# FPGA.net
KiCad netlist of a schematic drawn in Altium Designer
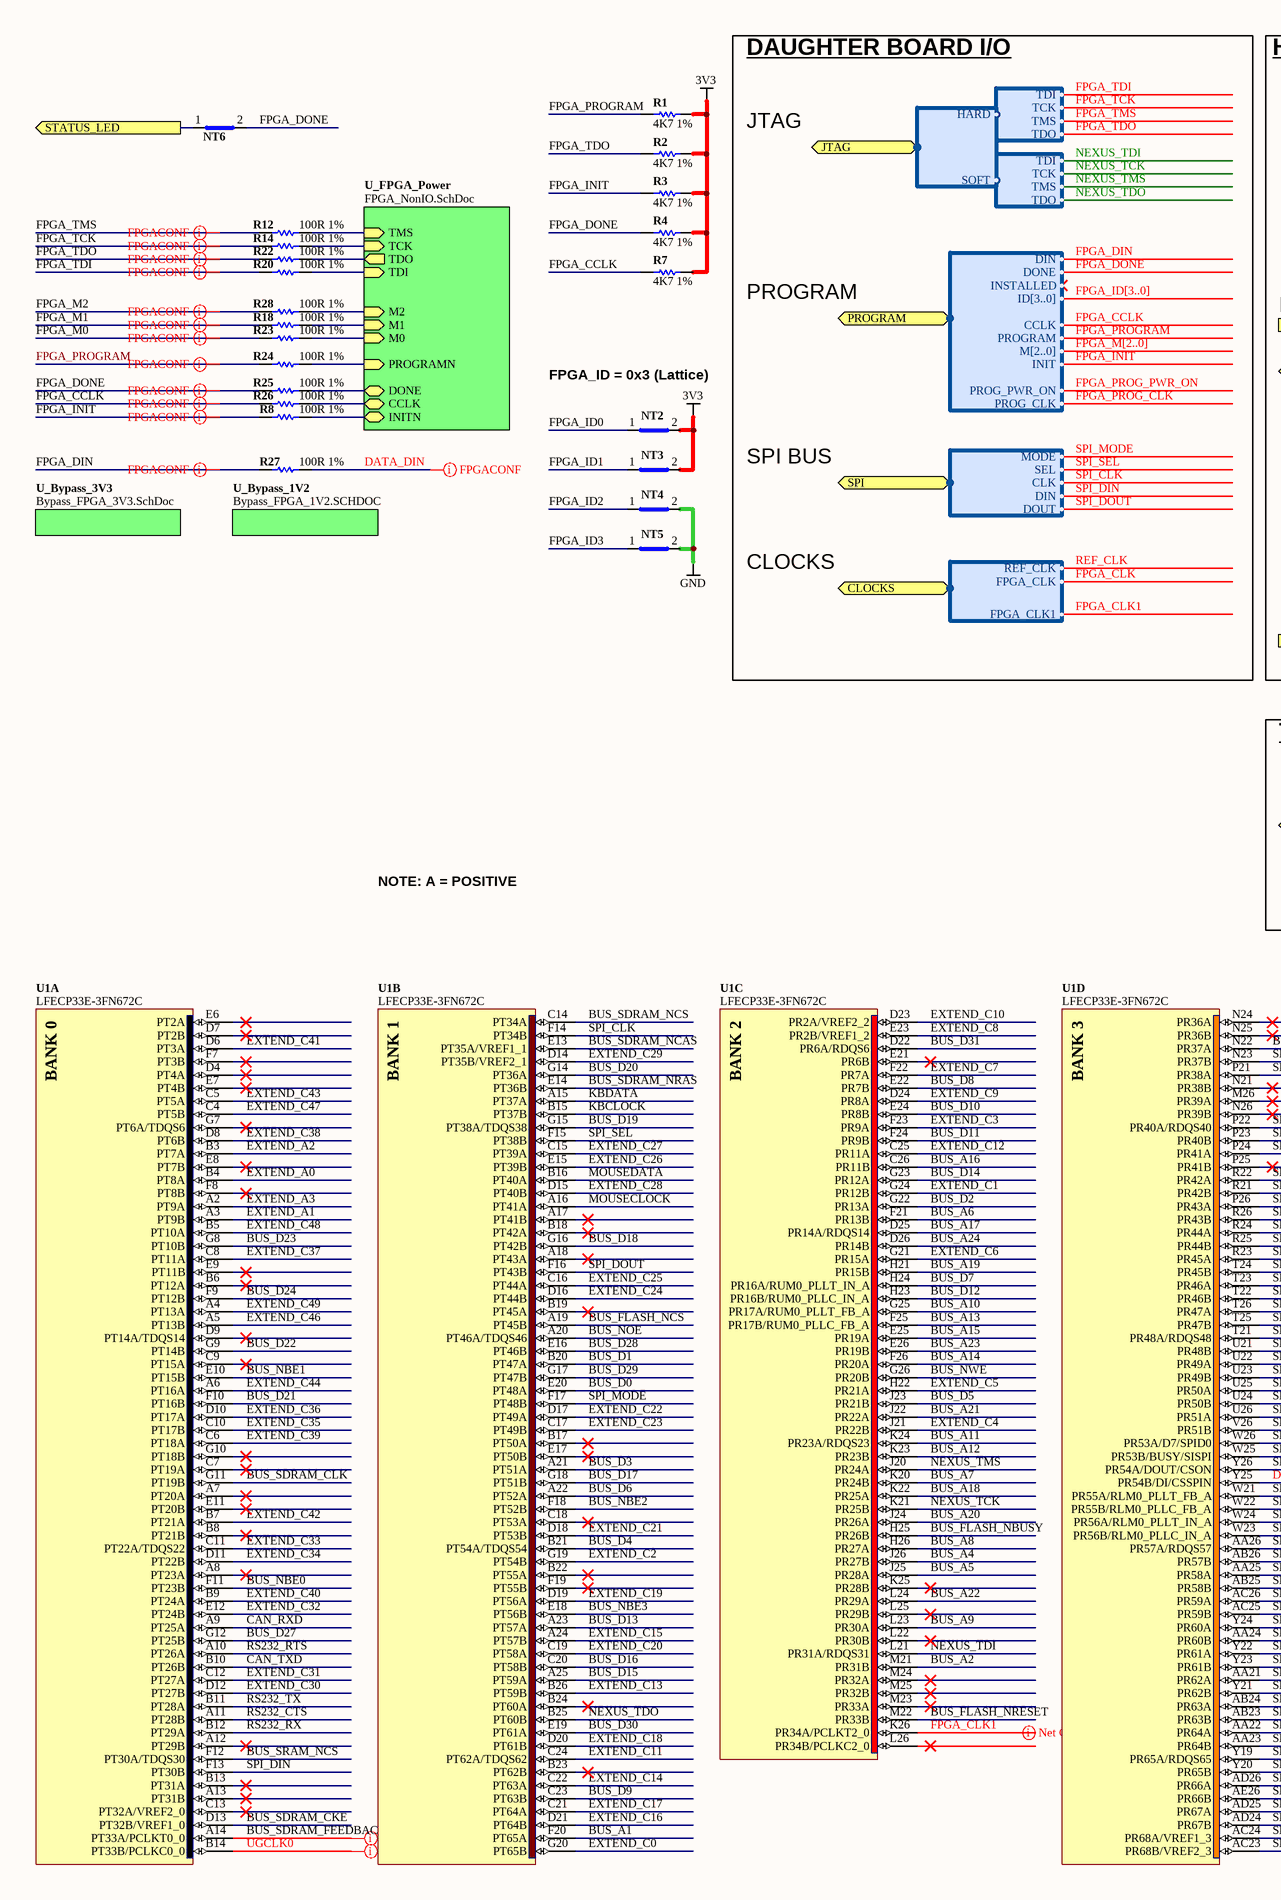
[diagram p0: FPGA.SCHDOC, left]
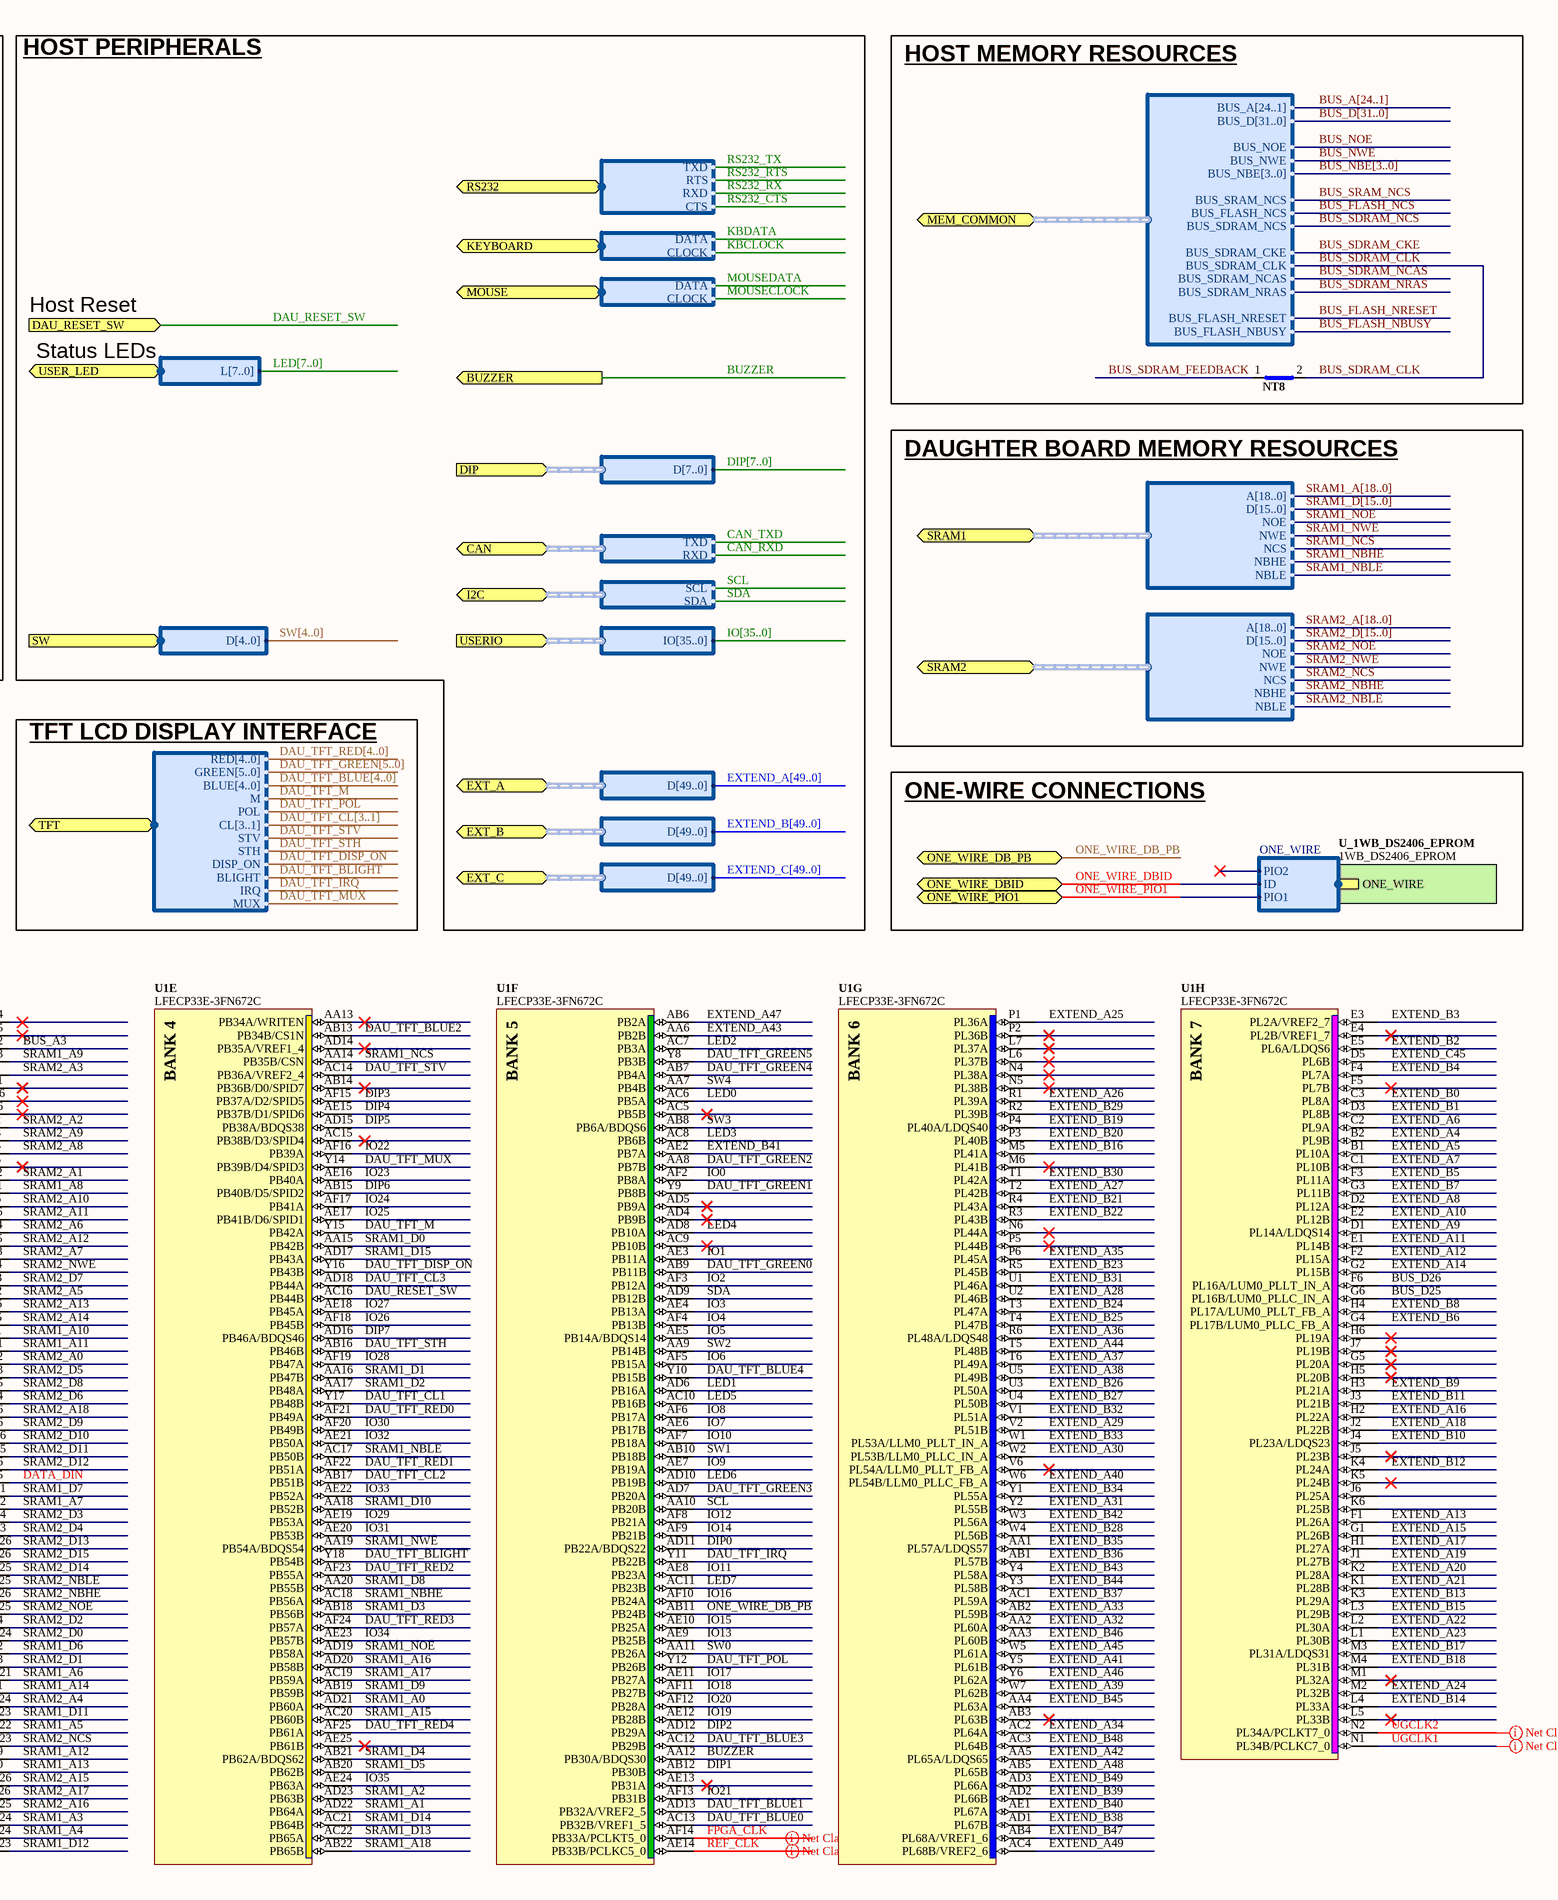
[diagram p1: FPGA.SCHDOC, right]

(export (version "E")
  (design (tool "Eeschema 10.0.6"))
  (components
    (comp (ref "NT2")
      (value "Net Tie SMT2")
      (footprint "NETTIE-SMT2-8X8")
      (description "Net-Tie, Surface Mount, 2 x 0.4mm x 0.2mm SMT Pads - For 0.2mm Track")
      (libsource (lib "AltiumDesignLibrary") (part "NETTIE-SMT2"))
    )
    (comp (ref "NT3")
      (value "Net Tie SMT2")
      (footprint "NETTIE-SMT2-8X8")
      (description "Net-Tie, Surface Mount, 2 x 0.4mm x 0.2mm SMT Pads - For 0.2mm Track")
      (libsource (lib "AltiumDesignLibrary") (part "NETTIE-SMT2"))
    )
    (comp (ref "NT4")
      (value "Net Tie SMT2")
      (footprint "NETTIE-SMT2-8X8")
      (description "Net-Tie, Surface Mount, 2 x 0.4mm x 0.2mm SMT Pads - For 0.2mm Track")
      (libsource (lib "AltiumDesignLibrary") (part "NETTIE-SMT2"))
    )
    (comp (ref "NT5")
      (value "Net Tie SMT2")
      (footprint "NETTIE-SMT2-8X8")
      (description "Net-Tie, Surface Mount, 2 x 0.4mm x 0.2mm SMT Pads - For 0.2mm Track")
      (libsource (lib "AltiumDesignLibrary") (part "NETTIE-SMT2"))
    )
    (comp (ref "NT6")
      (value "Net Tie SMT2")
      (footprint "NETTIE-SMT2-8X8")
      (description "Net-Tie, Surface Mount, 2 x 0.4mm x 0.2mm SMT Pads - For 0.2mm Track")
      (libsource (lib "AltiumDesignLibrary") (part "NETTIE-SMT2"))
    )
    (comp (ref "NT8")
      (value "Net Tie SMT2")
      (footprint "NETTIE-SMT2-8X8")
      (description "Net-Tie, Surface Mount, 2 x 0.4mm x 0.2mm SMT Pads - For 0.2mm Track")
      (libsource (lib "AltiumDesignLibrary") (part "NETTIE-SMT2"))
    )
    (comp (ref "R1")
      (value "4K7 1%")
      (footprint "RESC1005-STAR")
      (description "Resistor, 4K7 1% 0402 (1005)")
      (fields (field (name "TOLERANCE") "1 %"))
      (libsource (lib "AltiumDesignLibrary") (part "RES"))
    )
    (comp (ref "R2")
      (value "4K7 1%")
      (footprint "RESC1005-STAR")
      (description "Resistor, 4K7 1% 0402 (1005)")
      (fields (field (name "TOLERANCE") "1 %"))
      (libsource (lib "AltiumDesignLibrary") (part "RES"))
    )
    (comp (ref "R3")
      (value "4K7 1%")
      (footprint "RESC1005-STAR")
      (description "Resistor, 4K7 1% 0402 (1005)")
      (fields (field (name "TOLERANCE") "1 %"))
      (libsource (lib "AltiumDesignLibrary") (part "RES"))
    )
    (comp (ref "R4")
      (value "4K7 1%")
      (footprint "RESC1005-STAR")
      (description "Resistor, 4K7 1% 0402 (1005)")
      (fields (field (name "TOLERANCE") "1 %"))
      (libsource (lib "AltiumDesignLibrary") (part "RES"))
    )
    (comp (ref "R7")
      (value "4K7 1%")
      (footprint "RESC1005-STAR")
      (description "Resistor, 4K7 1% 0402 (1005)")
      (fields (field (name "TOLERANCE") "1 %"))
      (libsource (lib "AltiumDesignLibrary") (part "RES"))
    )
    (comp (ref "R8")
      (value "100R 1%")
      (footprint "RESC1005-STAR")
      (description "Resistor, 100R 1% 0402 (1005)")
      (fields (field (name "TOLERANCE") "1 %"))
      (libsource (lib "AltiumDesignLibrary") (part "RES"))
    )
    (comp (ref "R12")
      (value "100R 1%")
      (footprint "RESC1005-STAR")
      (description "Resistor, 100R 1% 0402 (1005)")
      (fields (field (name "TOLERANCE") "1 %"))
      (libsource (lib "AltiumDesignLibrary") (part "RES"))
    )
    (comp (ref "R14")
      (value "100R 1%")
      (footprint "RESC1005-STAR")
      (description "Resistor, 100R 1% 0402 (1005)")
      (fields (field (name "TOLERANCE") "1 %"))
      (libsource (lib "AltiumDesignLibrary") (part "RES"))
    )
    (comp (ref "R18")
      (value "100R 1%")
      (footprint "RESC1005-STAR")
      (description "Resistor, 100R 1% 0402 (1005)")
      (fields (field (name "TOLERANCE") "1 %"))
      (libsource (lib "AltiumDesignLibrary") (part "RES"))
    )
    (comp (ref "R20")
      (value "100R 1%")
      (footprint "RESC1005-STAR")
      (description "Resistor, 100R 1% 0402 (1005)")
      (fields (field (name "TOLERANCE") "1 %"))
      (libsource (lib "AltiumDesignLibrary") (part "RES"))
    )
    (comp (ref "R22")
      (value "100R 1%")
      (footprint "RESC1005-STAR")
      (description "Resistor, 100R 1% 0402 (1005)")
      (fields (field (name "TOLERANCE") "1 %"))
      (libsource (lib "AltiumDesignLibrary") (part "RES"))
    )
    (comp (ref "R23")
      (value "100R 1%")
      (footprint "RESC1005-STAR")
      (description "Resistor, 100R 1% 0402 (1005)")
      (fields (field (name "TOLERANCE") "1 %"))
      (libsource (lib "AltiumDesignLibrary") (part "RES"))
    )
    (comp (ref "R24")
      (value "100R 1%")
      (footprint "RESC1005-STAR")
      (description "Resistor, 100R 1% 0402 (1005)")
      (fields (field (name "TOLERANCE") "1 %"))
      (libsource (lib "AltiumDesignLibrary") (part "RES"))
    )
    (comp (ref "R25")
      (value "100R 1%")
      (footprint "RESC1005-STAR")
      (description "Resistor, 100R 1% 0402 (1005)")
      (fields (field (name "TOLERANCE") "1 %"))
      (libsource (lib "AltiumDesignLibrary") (part "RES"))
    )
    (comp (ref "R26")
      (value "100R 1%")
      (footprint "RESC1005-STAR")
      (description "Resistor, 100R 1% 0402 (1005)")
      (fields (field (name "TOLERANCE") "1 %"))
      (libsource (lib "AltiumDesignLibrary") (part "RES"))
    )
    (comp (ref "R27")
      (value "100R 1%")
      (footprint "RESC1005-STAR")
      (description "Resistor, 100R 1% 0402 (1005)")
      (fields (field (name "TOLERANCE") "1 %"))
      (libsource (lib "AltiumDesignLibrary") (part "RES"))
    )
    (comp (ref "R28")
      (value "100R 1%")
      (footprint "RESC1005-STAR")
      (description "Resistor, 100R 1% 0402 (1005)")
      (fields (field (name "TOLERANCE") "1 %"))
      (libsource (lib "AltiumDesignLibrary") (part "RES"))
    )
    (comp (ref "U1")
      (value "LFECP33E-3FN672C")
      (footprint "BGA100P26X26-672")
      (description "FPGA, Lattice ECP-35 FN672")
      (libsource (lib "AltiumDesignLibrary") (part "LFECP33E-3FN672C"))
    )
  )
  (nets
    (net (code "18") (name "/BUS_A1") (class "Default")
      (node (ref "U1") (pin "F20") (pinfunction "PT65A_F20") (pintype "bidirectional"))
    )
    (net (code "19") (name "/BUS_A2") (class "Default")
      (node (ref "U1") (pin "M21") (pinfunction "PR31B_M21") (pintype "bidirectional"))
    )
    (net (code "20") (name "/BUS_A3") (class "Default")
      (node (ref "U1") (pin "N22") (pinfunction "PR37A_N22") (pintype "bidirectional"))
    )
    (net (code "21") (name "/BUS_A4") (class "Default")
      (node (ref "U1") (pin "J26") (pinfunction "PR27B_J26") (pintype "bidirectional"))
    )
    (net (code "22") (name "/BUS_A5") (class "Default")
      (node (ref "U1") (pin "J25") (pinfunction "PR28A_J25") (pintype "bidirectional"))
    )
    (net (code "23") (name "/BUS_A6") (class "Default")
      (node (ref "U1") (pin "F21") (pinfunction "PR13B_F21") (pintype "bidirectional"))
    )
    (net (code "24") (name "/BUS_A7") (class "Default")
      (node (ref "U1") (pin "K20") (pinfunction "PR24B_K20") (pintype "bidirectional"))
    )
    (net (code "25") (name "/BUS_A8") (class "Default")
      (node (ref "U1") (pin "H26") (pinfunction "PR27A_H26") (pintype "bidirectional"))
    )
    (net (code "26") (name "/BUS_A9") (class "Default")
      (node (ref "U1") (pin "L23") (pinfunction "PR30A_L23") (pintype "bidirectional"))
    )
    (net (code "27") (name "/BUS_A10") (class "Default")
      (node (ref "U1") (pin "G25") (pinfunction "PR17A/RUM0_PLLT_FB_A_G25") (pintype "bidirectional"))
    )
    (net (code "28") (name "/BUS_A11") (class "Default")
      (node (ref "U1") (pin "K24") (pinfunction "PR23A/RDQS23_K24") (pintype "bidirectional"))
    )
    (net (code "29") (name "/BUS_A12") (class "Default")
      (node (ref "U1") (pin "K23") (pinfunction "PR23B_K23") (pintype "bidirectional"))
    )
    (net (code "30") (name "/BUS_A13") (class "Default")
      (node (ref "U1") (pin "F25") (pinfunction "PR17B/RUM0_PLLC_FB_A_F25") (pintype "bidirectional"))
    )
    (net (code "31") (name "/BUS_A14") (class "Default")
      (node (ref "U1") (pin "F26") (pinfunction "PR20A_F26") (pintype "bidirectional"))
    )
    (net (code "32") (name "/BUS_A15") (class "Default")
      (node (ref "U1") (pin "E25") (pinfunction "PR19A_E25") (pintype "bidirectional"))
    )
    (net (code "33") (name "/BUS_A16") (class "Default")
      (node (ref "U1") (pin "C26") (pinfunction "PR11B_C26") (pintype "bidirectional"))
    )
    (net (code "34") (name "/BUS_A17") (class "Default")
      (node (ref "U1") (pin "D25") (pinfunction "PR14A/RDQS14_D25") (pintype "bidirectional"))
    )
    (net (code "35") (name "/BUS_A18") (class "Default")
      (node (ref "U1") (pin "K22") (pinfunction "PR25A_K22") (pintype "bidirectional"))
    )
    (net (code "36") (name "/BUS_A19") (class "Default")
      (node (ref "U1") (pin "H21") (pinfunction "PR15B_H21") (pintype "bidirectional"))
    )
    (net (code "37") (name "/BUS_A20") (class "Default")
      (node (ref "U1") (pin "J24") (pinfunction "PR26A_J24") (pintype "bidirectional"))
    )
    (net (code "38") (name "/BUS_A21") (class "Default")
      (node (ref "U1") (pin "J22") (pinfunction "PR22A_J22") (pintype "bidirectional"))
    )
    (net (code "39") (name "/BUS_A22") (class "Default")
      (node (ref "U1") (pin "L24") (pinfunction "PR29A_L24") (pintype "bidirectional"))
    )
    (net (code "40") (name "/BUS_A23") (class "Default")
      (node (ref "U1") (pin "E26") (pinfunction "PR19B_E26") (pintype "bidirectional"))
    )
    (net (code "41") (name "/BUS_A24") (class "Default")
      (node (ref "U1") (pin "D26") (pinfunction "PR14B_D26") (pintype "bidirectional"))
    )
    (net (code "42") (name "/BUS_D0") (class "Default")
      (node (ref "U1") (pin "E20") (pinfunction "PT48A_E20") (pintype "bidirectional"))
    )
    (net (code "43") (name "/BUS_D1") (class "Default")
      (node (ref "U1") (pin "B20") (pinfunction "PT47A_B20") (pintype "bidirectional"))
    )
    (net (code "44") (name "/BUS_D2") (class "Default")
      (node (ref "U1") (pin "G22") (pinfunction "PR13A_G22") (pintype "bidirectional"))
    )
    (net (code "45") (name "/BUS_D3") (class "Default")
      (node (ref "U1") (pin "A21") (pinfunction "PT51A_A21") (pintype "bidirectional"))
    )
    (net (code "46") (name "/BUS_D4") (class "Default")
      (node (ref "U1") (pin "B21") (pinfunction "PT54A/TDQS54_B21") (pintype "bidirectional"))
    )
    (net (code "47") (name "/BUS_D5") (class "Default")
      (node (ref "U1") (pin "J23") (pinfunction "PR21B_J23") (pintype "bidirectional"))
    )
    (net (code "48") (name "/BUS_D6") (class "Default")
      (node (ref "U1") (pin "A22") (pinfunction "PT52A_A22") (pintype "bidirectional"))
    )
    (net (code "49") (name "/BUS_D7") (class "Default")
      (node (ref "U1") (pin "H24") (pinfunction "PR16A/RUM0_PLLT_IN_A_H24") (pintype "bidirectional"))
    )
    (net (code "50") (name "/BUS_D8") (class "Default")
      (node (ref "U1") (pin "E22") (pinfunction "PR7B_E22") (pintype "bidirectional"))
    )
    (net (code "51") (name "/BUS_D9") (class "Default")
      (node (ref "U1") (pin "C23") (pinfunction "PT63B_C23") (pintype "bidirectional"))
    )
    (net (code "52") (name "/BUS_D10") (class "Default")
      (node (ref "U1") (pin "E24") (pinfunction "PR8B_E24") (pintype "bidirectional"))
    )
    (net (code "53") (name "/BUS_D11") (class "Default")
      (node (ref "U1") (pin "F24") (pinfunction "PR9B_F24") (pintype "bidirectional"))
    )
    (net (code "54") (name "/BUS_D12") (class "Default")
      (node (ref "U1") (pin "H23") (pinfunction "PR16B/RUM0_PLLC_IN_A_H23") (pintype "bidirectional"))
    )
    (net (code "55") (name "/BUS_D13") (class "Default")
      (node (ref "U1") (pin "A23") (pinfunction "PT57A_A23") (pintype "bidirectional"))
    )
    (net (code "56") (name "/BUS_D14") (class "Default")
      (node (ref "U1") (pin "G23") (pinfunction "PR12A_G23") (pintype "bidirectional"))
    )
    (net (code "57") (name "/BUS_D15") (class "Default")
      (node (ref "U1") (pin "A25") (pinfunction "PT59A_A25") (pintype "bidirectional"))
    )
    (net (code "58") (name "/BUS_D16") (class "Default")
      (node (ref "U1") (pin "C20") (pinfunction "PT58B_C20") (pintype "bidirectional"))
    )
    (net (code "59") (name "/BUS_D17") (class "Default")
      (node (ref "U1") (pin "G18") (pinfunction "PT51B_G18") (pintype "bidirectional"))
    )
    (net (code "60") (name "/BUS_D18") (class "Default")
      (node (ref "U1") (pin "G16") (pinfunction "PT42B_G16") (pintype "bidirectional"))
    )
    (net (code "61") (name "/BUS_D19") (class "Default")
      (node (ref "U1") (pin "G15") (pinfunction "PT38A/TDQS38_G15") (pintype "bidirectional"))
    )
    (net (code "62") (name "/BUS_D20") (class "Default")
      (node (ref "U1") (pin "G14") (pinfunction "PT36A_G14") (pintype "bidirectional"))
    )
    (net (code "63") (name "/BUS_D21") (class "Default")
      (node (ref "U1") (pin "F10") (pinfunction "PT16B_F10") (pintype "bidirectional"))
    )
    (net (code "64") (name "/BUS_D22") (class "Default")
      (node (ref "U1") (pin "G9") (pinfunction "PT14B_G9") (pintype "bidirectional"))
    )
    (net (code "65") (name "/BUS_D23") (class "Default")
      (node (ref "U1") (pin "G8") (pinfunction "PT10B_G8") (pintype "bidirectional"))
    )
    (net (code "66") (name "/BUS_D24") (class "Default")
      (node (ref "U1") (pin "F9") (pinfunction "PT12B_F9") (pintype "bidirectional"))
    )
    (net (code "67") (name "/BUS_D25") (class "Default")
      (node (ref "U1") (pin "G6") (pinfunction "PL16B/LUM0_PLLC_IN_A_G6") (pintype "bidirectional"))
    )
    (net (code "68") (name "/BUS_D26") (class "Default")
      (node (ref "U1") (pin "F6") (pinfunction "PL16A/LUM0_PLLT_IN_A_F6") (pintype "bidirectional"))
    )
    (net (code "69") (name "/BUS_D27") (class "Default")
      (node (ref "U1") (pin "G12") (pinfunction "PT25B_G12") (pintype "bidirectional"))
    )
    (net (code "70") (name "/BUS_D28") (class "Default")
      (node (ref "U1") (pin "E16") (pinfunction "PT46B_E16") (pintype "bidirectional"))
    )
    (net (code "71") (name "/BUS_D29") (class "Default")
      (node (ref "U1") (pin "G17") (pinfunction "PT47B_G17") (pintype "bidirectional"))
    )
    (net (code "72") (name "/BUS_D30") (class "Default")
      (node (ref "U1") (pin "E19") (pinfunction "PT61A_E19") (pintype "bidirectional"))
    )
    (net (code "73") (name "/BUS_D31") (class "Default")
      (node (ref "U1") (pin "D22") (pinfunction "PR6A/RDQS6_D22") (pintype "bidirectional"))
    )
    (net (code "75") (name "/BUS_FLASH_NBUSY") (class "Default")
      (node (ref "U1") (pin "H25") (pinfunction "PR26B_H25") (pintype "bidirectional"))
    )
    (net (code "76") (name "/BUS_FLASH_NCS") (class "Default")
      (node (ref "U1") (pin "A19") (pinfunction "PT45B_A19") (pintype "bidirectional"))
    )
    (net (code "77") (name "/BUS_FLASH_NRESET") (class "Default")
      (node (ref "U1") (pin "M22") (pinfunction "PR33B_M22") (pintype "bidirectional"))
    )
    (net (code "78") (name "/BUS_NBE0") (class "Default")
      (node (ref "U1") (pin "F11") (pinfunction "PT23B_F11") (pintype "bidirectional"))
    )
    (net (code "79") (name "/BUS_NBE1") (class "Default")
      (node (ref "U1") (pin "E10") (pinfunction "PT15B_E10") (pintype "bidirectional"))
    )
    (net (code "80") (name "/BUS_NBE2") (class "Default")
      (node (ref "U1") (pin "F18") (pinfunction "PT52B_F18") (pintype "bidirectional"))
    )
    (net (code "81") (name "/BUS_NBE3") (class "Default")
      (node (ref "U1") (pin "E18") (pinfunction "PT56B_E18") (pintype "bidirectional"))
    )
    (net (code "83") (name "/BUS_NOE") (class "Default")
      (node (ref "U1") (pin "A20") (pinfunction "PT46A/TDQS46_A20") (pintype "bidirectional"))
    )
    (net (code "84") (name "/BUS_NWE") (class "Default")
      (node (ref "U1") (pin "G26") (pinfunction "PR20B_G26") (pintype "bidirectional"))
    )
    (net (code "85") (name "/BUS_SDRAM_CKE") (class "Default")
      (node (ref "U1") (pin "D13") (pinfunction "PT32B/VREF1_0_D13") (pintype "bidirectional"))
    )
    (net (code "86") (name "/BUS_SDRAM_CLK") (class "Default")
      (node (ref "NT8") (pin "2") (pinfunction "Net2_2") (pintype "passive"))
      (node (ref "U1") (pin "G11") (pinfunction "PT19B_G11") (pintype "bidirectional"))
    )
    (net (code "87") (name "/BUS_SDRAM_FEEDBACK") (class "Default")
      (node (ref "NT8") (pin "1") (pinfunction "Net1_1") (pintype "passive"))
      (node (ref "U1") (pin "A14") (pinfunction "PT33A/PCLKT0_0_A14") (pintype "bidirectional"))
    )
    (net (code "88") (name "/BUS_SDRAM_NCAS") (class "Default")
      (node (ref "U1") (pin "E13") (pinfunction "PT35A/VREF1_1_E13") (pintype "bidirectional"))
    )
    (net (code "89") (name "/BUS_SDRAM_NCS") (class "Default")
      (node (ref "U1") (pin "C14") (pinfunction "PT34A_C14") (pintype "bidirectional"))
    )
    (net (code "90") (name "/BUS_SDRAM_NRAS") (class "Default")
      (node (ref "U1") (pin "E14") (pinfunction "PT36B_E14") (pintype "bidirectional"))
    )
    (net (code "91") (name "/BUS_SRAM_NCS") (class "Default")
      (node (ref "U1") (pin "F12") (pinfunction "PT30A/TDQS30_F12") (pintype "bidirectional"))
    )
    (net (code "92") (name "/BUZZER") (class "Default")
      (node (ref "U1") (pin "AA12") (pinfunction "PB30A/BDQS30_AA12") (pintype "bidirectional"))
    )
    (net (code "93") (name "/CAN_RXD") (class "Default")
      (node (ref "U1") (pin "A9") (pinfunction "PT25A_A9") (pintype "bidirectional"))
    )
    (net (code "94") (name "/CAN_TXD") (class "Default")
      (node (ref "U1") (pin "B10") (pinfunction "PT26B_B10") (pintype "bidirectional"))
    )
    (net (code "95") (name "/CCLK") (class "Default")
      (node (ref "R26") (pin "2") (pinfunction "2_2") (pintype "passive"))
    )
    (net (code "96") (name "/DATA_DIN") (class "Default")
      (node (ref "R27") (pin "2") (pinfunction "2_2") (pintype "passive"))
      (node (ref "U1") (pin "Y25") (pinfunction "PR54B/DI/CSSPIN_Y25") (pintype "bidirectional"))
    )
    (net (code "97") (name "/DAU_RESET_SW") (class "Default")
      (node (ref "U1") (pin "AC16") (pinfunction "PB44B_AC16") (pintype "bidirectional"))
    )
    (net (code "98") (name "/DAU_TFT_BLIGHT") (class "Default")
      (node (ref "U1") (pin "Y18") (pinfunction "PB54B_Y18") (pintype "bidirectional"))
    )
    (net (code "99") (name "/DAU_TFT_BLUE0") (class "Default")
      (node (ref "U1") (pin "AC13") (pinfunction "PB32B/VREF1_5_AC13") (pintype "bidirectional"))
    )
    (net (code "100") (name "/DAU_TFT_BLUE1") (class "Default")
      (node (ref "U1") (pin "AD13") (pinfunction "PB32A/VREF2_5_AD13") (pintype "bidirectional"))
    )
    (net (code "101") (name "/DAU_TFT_BLUE2") (class "Default")
      (node (ref "U1") (pin "AB13") (pinfunction "PB34B/CS1N_AB13") (pintype "bidirectional"))
    )
    (net (code "102") (name "/DAU_TFT_BLUE3") (class "Default")
      (node (ref "U1") (pin "AC12") (pinfunction "PB29B_AC12") (pintype "bidirectional"))
    )
    (net (code "103") (name "/DAU_TFT_BLUE4") (class "Default")
      (node (ref "U1") (pin "Y10") (pinfunction "PB15B_Y10") (pintype "bidirectional"))
    )
    (net (code "105") (name "/DAU_TFT_CL1") (class "Default")
      (node (ref "U1") (pin "Y17") (pinfunction "PB48B_Y17") (pintype "bidirectional"))
    )
    (net (code "106") (name "/DAU_TFT_CL2") (class "Default")
      (node (ref "U1") (pin "AB17") (pinfunction "PB51B_AB17") (pintype "bidirectional"))
    )
    (net (code "107") (name "/DAU_TFT_CL3") (class "Default")
      (node (ref "U1") (pin "AD18") (pinfunction "PB44A_AD18") (pintype "bidirectional"))
    )
    (net (code "108") (name "/DAU_TFT_DISP_ON") (class "Default")
      (node (ref "U1") (pin "Y16") (pinfunction "PB43B_Y16") (pintype "bidirectional"))
    )
    (net (code "109") (name "/DAU_TFT_GREEN0") (class "Default")
      (node (ref "U1") (pin "AB9") (pinfunction "PB11B_AB9") (pintype "bidirectional"))
    )
    (net (code "110") (name "/DAU_TFT_GREEN1") (class "Default")
      (node (ref "U1") (pin "Y9") (pinfunction "PB8B_Y9") (pintype "bidirectional"))
    )
    (net (code "111") (name "/DAU_TFT_GREEN2") (class "Default")
      (node (ref "U1") (pin "AA8") (pinfunction "PB7B_AA8") (pintype "bidirectional"))
    )
    (net (code "112") (name "/DAU_TFT_GREEN3") (class "Default")
      (node (ref "U1") (pin "AD7") (pinfunction "PB20A_AD7") (pintype "bidirectional"))
    )
    (net (code "113") (name "/DAU_TFT_GREEN4") (class "Default")
      (node (ref "U1") (pin "AB7") (pinfunction "PB4A_AB7") (pintype "bidirectional"))
    )
    (net (code "114") (name "/DAU_TFT_GREEN5") (class "Default")
      (node (ref "U1") (pin "Y8") (pinfunction "PB3B_Y8") (pintype "bidirectional"))
    )
    (net (code "116") (name "/DAU_TFT_IRQ") (class "Default")
      (node (ref "U1") (pin "Y11") (pinfunction "PB22B_Y11") (pintype "bidirectional"))
    )
    (net (code "117") (name "/DAU_TFT_M") (class "Default")
      (node (ref "U1") (pin "Y15") (pinfunction "PB42A_Y15") (pintype "bidirectional"))
    )
    (net (code "118") (name "/DAU_TFT_MUX") (class "Default")
      (node (ref "U1") (pin "Y14") (pinfunction "PB39B/D4/SPID3_Y14") (pintype "bidirectional"))
    )
    (net (code "119") (name "/DAU_TFT_POL") (class "Default")
      (node (ref "U1") (pin "Y12") (pinfunction "PB26B_Y12") (pintype "bidirectional"))
    )
    (net (code "120") (name "/DAU_TFT_RED0") (class "Default")
      (node (ref "U1") (pin "AF21") (pinfunction "PB49A_AF21") (pintype "bidirectional"))
    )
    (net (code "121") (name "/DAU_TFT_RED1") (class "Default")
      (node (ref "U1") (pin "AF22") (pinfunction "PB51A_AF22") (pintype "bidirectional"))
    )
    (net (code "122") (name "/DAU_TFT_RED2") (class "Default")
      (node (ref "U1") (pin "AF23") (pinfunction "PB55A_AF23") (pintype "bidirectional"))
    )
    (net (code "123") (name "/DAU_TFT_RED3") (class "Default")
      (node (ref "U1") (pin "AF24") (pinfunction "PB57A_AF24") (pintype "bidirectional"))
    )
    (net (code "124") (name "/DAU_TFT_RED4") (class "Default")
      (node (ref "U1") (pin "AF25") (pinfunction "PB61A_AF25") (pintype "bidirectional"))
    )
    (net (code "126") (name "/DAU_TFT_STH") (class "Default")
      (node (ref "U1") (pin "AB16") (pinfunction "PB46B_AB16") (pintype "bidirectional"))
    )
    (net (code "127") (name "/DAU_TFT_STV") (class "Default")
      (node (ref "U1") (pin "AC14") (pinfunction "PB36A/VREF2_4_AC14") (pintype "bidirectional"))
    )
    (net (code "128") (name "/DIP0") (class "Default")
      (node (ref "U1") (pin "AD11") (pinfunction "PB22A/BDQS22_AD11") (pintype "bidirectional"))
    )
    (net (code "129") (name "/DIP1") (class "Default")
      (node (ref "U1") (pin "AB12") (pinfunction "PB30B_AB12") (pintype "bidirectional"))
    )
    (net (code "130") (name "/DIP2") (class "Default")
      (node (ref "U1") (pin "AD12") (pinfunction "PB29A_AD12") (pintype "bidirectional"))
    )
    (net (code "131") (name "/DIP3") (class "Default")
      (node (ref "U1") (pin "AF15") (pinfunction "PB37A/D2/SPID5_AF15") (pintype "bidirectional"))
    )
    (net (code "132") (name "/DIP4") (class "Default")
      (node (ref "U1") (pin "AE15") (pinfunction "PB37B/D1/SPID6_AE15") (pintype "bidirectional"))
    )
    (net (code "133") (name "/DIP5") (class "Default")
      (node (ref "U1") (pin "AD15") (pinfunction "PB38A/BDQS38_AD15") (pintype "bidirectional"))
    )
    (net (code "134") (name "/DIP6") (class "Default")
      (node (ref "U1") (pin "AB15") (pinfunction "PB40B/D5/SPID2_AB15") (pintype "bidirectional"))
    )
    (net (code "135") (name "/DIP7") (class "Default")
      (node (ref "U1") (pin "AD16") (pinfunction "PB46A/BDQS46_AD16") (pintype "bidirectional"))
    )
    (net (code "137") (name "/DONE") (class "Default")
      (node (ref "R25") (pin "2") (pinfunction "2_2") (pintype "passive"))
    )
    (net (code "138") (name "/EXTEND_A0") (class "Default")
      (node (ref "U1") (pin "B4") (pinfunction "PT8A_B4") (pintype "bidirectional"))
    )
    (net (code "139") (name "/EXTEND_A1") (class "Default")
      (node (ref "U1") (pin "A3") (pinfunction "PT9B_A3") (pintype "bidirectional"))
    )
    (net (code "140") (name "/EXTEND_A2") (class "Default")
      (node (ref "U1") (pin "B3") (pinfunction "PT7A_B3") (pintype "bidirectional"))
    )
    (net (code "141") (name "/EXTEND_A3") (class "Default")
      (node (ref "U1") (pin "A2") (pinfunction "PT9A_A2") (pintype "bidirectional"))
    )
    (net (code "142") (name "/EXTEND_A4") (class "Default")
      (node (ref "U1") (pin "B2") (pinfunction "PL9B_B2") (pintype "bidirectional"))
    )
    (net (code "143") (name "/EXTEND_A5") (class "Default")
      (node (ref "U1") (pin "B1") (pinfunction "PL10A_B1") (pintype "bidirectional"))
    )
    (net (code "144") (name "/EXTEND_A6") (class "Default")
      (node (ref "U1") (pin "C2") (pinfunction "PL9A_C2") (pintype "bidirectional"))
    )
    (net (code "145") (name "/EXTEND_A7") (class "Default")
      (node (ref "U1") (pin "C1") (pinfunction "PL10B_C1") (pintype "bidirectional"))
    )
    (net (code "146") (name "/EXTEND_A8") (class "Default")
      (node (ref "U1") (pin "D2") (pinfunction "PL12A_D2") (pintype "bidirectional"))
    )
    (net (code "147") (name "/EXTEND_A9") (class "Default")
      (node (ref "U1") (pin "D1") (pinfunction "PL14A/LDQS14_D1") (pintype "bidirectional"))
    )
    (net (code "148") (name "/EXTEND_A10") (class "Default")
      (node (ref "U1") (pin "E2") (pinfunction "PL12B_E2") (pintype "bidirectional"))
    )
    (net (code "149") (name "/EXTEND_A11") (class "Default")
      (node (ref "U1") (pin "E1") (pinfunction "PL14B_E1") (pintype "bidirectional"))
    )
    (net (code "150") (name "/EXTEND_A12") (class "Default")
      (node (ref "U1") (pin "F2") (pinfunction "PL15A_F2") (pintype "bidirectional"))
    )
    (net (code "151") (name "/EXTEND_A13") (class "Default")
      (node (ref "U1") (pin "F1") (pinfunction "PL26A_F1") (pintype "bidirectional"))
    )
    (net (code "152") (name "/EXTEND_A14") (class "Default")
      (node (ref "U1") (pin "G2") (pinfunction "PL15B_G2") (pintype "bidirectional"))
    )
    (net (code "153") (name "/EXTEND_A15") (class "Default")
      (node (ref "U1") (pin "G1") (pinfunction "PL26B_G1") (pintype "bidirectional"))
    )
    (net (code "154") (name "/EXTEND_A16") (class "Default")
      (node (ref "U1") (pin "H2") (pinfunction "PL22A_H2") (pintype "bidirectional"))
    )
    (net (code "155") (name "/EXTEND_A17") (class "Default")
      (node (ref "U1") (pin "H1") (pinfunction "PL27A_H1") (pintype "bidirectional"))
    )
    (net (code "156") (name "/EXTEND_A18") (class "Default")
      (node (ref "U1") (pin "J2") (pinfunction "PL22B_J2") (pintype "bidirectional"))
    )
    (net (code "157") (name "/EXTEND_A19") (class "Default")
      (node (ref "U1") (pin "J1") (pinfunction "PL27B_J1") (pintype "bidirectional"))
    )
    (net (code "158") (name "/EXTEND_A20") (class "Default")
      (node (ref "U1") (pin "K2") (pinfunction "PL28A_K2") (pintype "bidirectional"))
    )
    (net (code "159") (name "/EXTEND_A21") (class "Default")
      (node (ref "U1") (pin "K1") (pinfunction "PL28B_K1") (pintype "bidirectional"))
    )
    (net (code "160") (name "/EXTEND_A22") (class "Default")
      (node (ref "U1") (pin "L2") (pinfunction "PL30A_L2") (pintype "bidirectional"))
    )
    (net (code "161") (name "/EXTEND_A23") (class "Default")
      (node (ref "U1") (pin "L1") (pinfunction "PL30B_L1") (pintype "bidirectional"))
    )
    (net (code "162") (name "/EXTEND_A24") (class "Default")
      (node (ref "U1") (pin "M2") (pinfunction "PL32B_M2") (pintype "bidirectional"))
    )
    (net (code "163") (name "/EXTEND_A25") (class "Default")
      (node (ref "U1") (pin "P1") (pinfunction "PL36A_P1") (pintype "bidirectional"))
    )
    (net (code "164") (name "/EXTEND_A26") (class "Default")
      (node (ref "U1") (pin "R1") (pinfunction "PL39A_R1") (pintype "bidirectional"))
    )
    (net (code "165") (name "/EXTEND_A27") (class "Default")
      (node (ref "U1") (pin "T2") (pinfunction "PL42B_T2") (pintype "bidirectional"))
    )
    (net (code "166") (name "/EXTEND_A28") (class "Default")
      (node (ref "U1") (pin "U2") (pinfunction "PL46B_U2") (pintype "bidirectional"))
    )
    (net (code "167") (name "/EXTEND_A29") (class "Default")
      (node (ref "U1") (pin "V2") (pinfunction "PL51B_V2") (pintype "bidirectional"))
    )
    (net (code "168") (name "/EXTEND_A30") (class "Default")
      (node (ref "U1") (pin "W2") (pinfunction "PL53B/LLM0_PLLC_IN_A_W2") (pintype "bidirectional"))
    )
    (net (code "169") (name "/EXTEND_A31") (class "Default")
      (node (ref "U1") (pin "Y2") (pinfunction "PL55B_Y2") (pintype "bidirectional"))
    )
    (net (code "170") (name "/EXTEND_A32") (class "Default")
      (node (ref "U1") (pin "AA2") (pinfunction "PL60A_AA2") (pintype "bidirectional"))
    )
    (net (code "171") (name "/EXTEND_A33") (class "Default")
      (node (ref "U1") (pin "AB2") (pinfunction "PL59B_AB2") (pintype "bidirectional"))
    )
    (net (code "172") (name "/EXTEND_A34") (class "Default")
      (node (ref "U1") (pin "AC2") (pinfunction "PL64A_AC2") (pintype "bidirectional"))
    )
    (net (code "173") (name "/EXTEND_A35") (class "Default")
      (node (ref "U1") (pin "P6") (pinfunction "PL45A_P6") (pintype "bidirectional"))
    )
    (net (code "174") (name "/EXTEND_A36") (class "Default")
      (node (ref "U1") (pin "R6") (pinfunction "PL48A/LDQS48_R6") (pintype "bidirectional"))
    )
    (net (code "175") (name "/EXTEND_A37") (class "Default")
      (node (ref "U1") (pin "T6") (pinfunction "PL49A_T6") (pintype "bidirectional"))
    )
    (net (code "176") (name "/EXTEND_A38") (class "Default")
      (node (ref "U1") (pin "U5") (pinfunction "PL49B_U5") (pintype "bidirectional"))
    )
    (net (code "177") (name "/EXTEND_A39") (class "Default")
      (node (ref "U1") (pin "W7") (pinfunction "PL62B_W7") (pintype "bidirectional"))
    )
    (net (code "178") (name "/EXTEND_A40") (class "Default")
      (node (ref "U1") (pin "W6") (pinfunction "PL54B/LLM0_PLLC_FB_A_W6") (pintype "bidirectional"))
    )
    (net (code "179") (name "/EXTEND_A41") (class "Default")
      (node (ref "U1") (pin "Y5") (pinfunction "PL61B_Y5") (pintype "bidirectional"))
    )
    (net (code "180") (name "/EXTEND_A42") (class "Default")
      (node (ref "U1") (pin "AA5") (pinfunction "PL65A/LDQS65_AA5") (pintype "bidirectional"))
    )
    (net (code "181") (name "/EXTEND_A43") (class "Default")
      (node (ref "U1") (pin "AA6") (pinfunction "PB2B_AA6") (pintype "bidirectional"))
    )
    (net (code "182") (name "/EXTEND_A44") (class "Default")
      (node (ref "U1") (pin "T5") (pinfunction "PL48B_T5") (pintype "bidirectional"))
    )
    (net (code "183") (name "/EXTEND_A45") (class "Default")
      (node (ref "U1") (pin "W5") (pinfunction "PL61A_W5") (pintype "bidirectional"))
    )
    (net (code "184") (name "/EXTEND_A46") (class "Default")
      (node (ref "U1") (pin "Y6") (pinfunction "PL62A_Y6") (pintype "bidirectional"))
    )
    (net (code "185") (name "/EXTEND_A47") (class "Default")
      (node (ref "U1") (pin "AB6") (pinfunction "PB2A_AB6") (pintype "bidirectional"))
    )
    (net (code "186") (name "/EXTEND_A48") (class "Default")
      (node (ref "U1") (pin "AB5") (pinfunction "PL65B_AB5") (pintype "bidirectional"))
    )
    (net (code "187") (name "/EXTEND_A49") (class "Default")
      (node (ref "U1") (pin "AC4") (pinfunction "PL68B/VREF2_6_AC4") (pintype "bidirectional"))
    )
    (net (code "189") (name "/EXTEND_B0") (class "Default")
      (node (ref "U1") (pin "C3") (pinfunction "PL8A_C3") (pintype "bidirectional"))
    )
    (net (code "190") (name "/EXTEND_B1") (class "Default")
      (node (ref "U1") (pin "D3") (pinfunction "PL8B_D3") (pintype "bidirectional"))
    )
    (net (code "191") (name "/EXTEND_B2") (class "Default")
      (node (ref "U1") (pin "E5") (pinfunction "PL6A/LDQS6_E5") (pintype "bidirectional"))
    )
    (net (code "192") (name "/EXTEND_B3") (class "Default")
      (node (ref "U1") (pin "E3") (pinfunction "PL2A/VREF2_7_E3") (pintype "bidirectional"))
    )
    (net (code "193") (name "/EXTEND_B4") (class "Default")
      (node (ref "U1") (pin "F4") (pinfunction "PL7A_F4") (pintype "bidirectional"))
    )
    (net (code "194") (name "/EXTEND_B5") (class "Default")
      (node (ref "U1") (pin "F3") (pinfunction "PL11A_F3") (pintype "bidirectional"))
    )
    (net (code "195") (name "/EXTEND_B6") (class "Default")
      (node (ref "U1") (pin "G4") (pinfunction "PL17B/LUM0_PLLC_FB_A_G4") (pintype "bidirectional"))
    )
    (net (code "196") (name "/EXTEND_B7") (class "Default")
      (node (ref "U1") (pin "G3") (pinfunction "PL11B_G3") (pintype "bidirectional"))
    )
    (net (code "197") (name "/EXTEND_B8") (class "Default")
      (node (ref "U1") (pin "H4") (pinfunction "PL17A/LUM0_PLLT_FB_A_H4") (pintype "bidirectional"))
    )
    (net (code "198") (name "/EXTEND_B9") (class "Default")
      (node (ref "U1") (pin "H3") (pinfunction "PL21A_H3") (pintype "bidirectional"))
    )
    (net (code "199") (name "/EXTEND_B10") (class "Default")
      (node (ref "U1") (pin "J4") (pinfunction "PL23A/LDQS23_J4") (pintype "bidirectional"))
    )
    (net (code "200") (name "/EXTEND_B11") (class "Default")
      (node (ref "U1") (pin "J3") (pinfunction "PL21B_J3") (pintype "bidirectional"))
    )
    (net (code "201") (name "/EXTEND_B12") (class "Default")
      (node (ref "U1") (pin "K4") (pinfunction "PL24A_K4") (pintype "bidirectional"))
    )
    (net (code "202") (name "/EXTEND_B13") (class "Default")
      (node (ref "U1") (pin "K3") (pinfunction "PL29A_K3") (pintype "bidirectional"))
    )
    (net (code "203") (name "/EXTEND_B14") (class "Default")
      (node (ref "U1") (pin "L4") (pinfunction "PL33A_L4") (pintype "bidirectional"))
    )
    (net (code "204") (name "/EXTEND_B15") (class "Default")
      (node (ref "U1") (pin "L3") (pinfunction "PL29B_L3") (pintype "bidirectional"))
    )
    (net (code "205") (name "/EXTEND_B16") (class "Default")
      (node (ref "U1") (pin "M5") (pinfunction "PL41A_M5") (pintype "bidirectional"))
    )
    (net (code "206") (name "/EXTEND_B17") (class "Default")
      (node (ref "U1") (pin "M3") (pinfunction "PL31A/LDQS31_M3") (pintype "bidirectional"))
    )
    (net (code "207") (name "/EXTEND_B18") (class "Default")
      (node (ref "U1") (pin "M4") (pinfunction "PL31B_M4") (pintype "bidirectional"))
    )
    (net (code "208") (name "/EXTEND_B19") (class "Default")
      (node (ref "U1") (pin "P4") (pinfunction "PL40A/LDQS40_P4") (pintype "bidirectional"))
    )
    (net (code "209") (name "/EXTEND_B20") (class "Default")
      (node (ref "U1") (pin "P3") (pinfunction "PL40B_P3") (pintype "bidirectional"))
    )
    (net (code "210") (name "/EXTEND_B21") (class "Default")
      (node (ref "U1") (pin "R4") (pinfunction "PL43A_R4") (pintype "bidirectional"))
    )
    (net (code "211") (name "/EXTEND_B22") (class "Default")
      (node (ref "U1") (pin "R3") (pinfunction "PL43B_R3") (pintype "bidirectional"))
    )
    (net (code "212") (name "/EXTEND_B23") (class "Default")
      (node (ref "U1") (pin "R5") (pinfunction "PL45B_R5") (pintype "bidirectional"))
    )
    (net (code "213") (name "/EXTEND_B24") (class "Default")
      (node (ref "U1") (pin "T3") (pinfunction "PL47A_T3") (pintype "bidirectional"))
    )
    (net (code "214") (name "/EXTEND_B25") (class "Default")
      (node (ref "U1") (pin "T4") (pinfunction "PL47B_T4") (pintype "bidirectional"))
    )
    (net (code "215") (name "/EXTEND_B26") (class "Default")
      (node (ref "U1") (pin "U3") (pinfunction "PL50A_U3") (pintype "bidirectional"))
    )
    (net (code "216") (name "/EXTEND_B27") (class "Default")
      (node (ref "U1") (pin "U4") (pinfunction "PL50B_U4") (pintype "bidirectional"))
    )
    (net (code "217") (name "/EXTEND_B28") (class "Default")
      (node (ref "U1") (pin "W4") (pinfunction "PL56B_W4") (pintype "bidirectional"))
    )
    (net (code "218") (name "/EXTEND_B29") (class "Default")
      (node (ref "U1") (pin "R2") (pinfunction "PL39B_R2") (pintype "bidirectional"))
    )
    (net (code "219") (name "/EXTEND_B30") (class "Default")
      (node (ref "U1") (pin "T1") (pinfunction "PL42A_T1") (pintype "bidirectional"))
    )
    (net (code "220") (name "/EXTEND_B31") (class "Default")
      (node (ref "U1") (pin "U1") (pinfunction "PL46A_U1") (pintype "bidirectional"))
    )
    (net (code "221") (name "/EXTEND_B32") (class "Default")
      (node (ref "U1") (pin "V1") (pinfunction "PL51A_V1") (pintype "bidirectional"))
    )
    (net (code "222") (name "/EXTEND_B33") (class "Default")
      (node (ref "U1") (pin "W1") (pinfunction "PL53A/LLM0_PLLT_IN_A_W1") (pintype "bidirectional"))
    )
    (net (code "223") (name "/EXTEND_B34") (class "Default")
      (node (ref "U1") (pin "Y1") (pinfunction "PL55A_Y1") (pintype "bidirectional"))
    )
    (net (code "224") (name "/EXTEND_B35") (class "Default")
      (node (ref "U1") (pin "AA1") (pinfunction "PL57A/LDQS57_AA1") (pintype "bidirectional"))
    )
    (net (code "225") (name "/EXTEND_B36") (class "Default")
      (node (ref "U1") (pin "AB1") (pinfunction "PL57B_AB1") (pintype "bidirectional"))
    )
    (net (code "226") (name "/EXTEND_B37") (class "Default")
      (node (ref "U1") (pin "AC1") (pinfunction "PL59A_AC1") (pintype "bidirectional"))
    )
    (net (code "227") (name "/EXTEND_B38") (class "Default")
      (node (ref "U1") (pin "AD1") (pinfunction "PL67B_AD1") (pintype "bidirectional"))
    )
    (net (code "228") (name "/EXTEND_B39") (class "Default")
      (node (ref "U1") (pin "AD2") (pinfunction "PL66B_AD2") (pintype "bidirectional"))
    )
    (net (code "229") (name "/EXTEND_B40") (class "Default")
      (node (ref "U1") (pin "AE1") (pinfunction "PL67A_AE1") (pintype "bidirectional"))
    )
    (net (code "230") (name "/EXTEND_B41") (class "Default")
      (node (ref "U1") (pin "AE2") (pinfunction "PB7A_AE2") (pintype "bidirectional"))
    )
    (net (code "231") (name "/EXTEND_B42") (class "Default")
      (node (ref "U1") (pin "W3") (pinfunction "PL56A_W3") (pintype "bidirectional"))
    )
    (net (code "232") (name "/EXTEND_B43") (class "Default")
      (node (ref "U1") (pin "Y4") (pinfunction "PL58A_Y4") (pintype "bidirectional"))
    )
    (net (code "233") (name "/EXTEND_B44") (class "Default")
      (node (ref "U1") (pin "Y3") (pinfunction "PL58B_Y3") (pintype "bidirectional"))
    )
    (net (code "234") (name "/EXTEND_B45") (class "Default")
      (node (ref "U1") (pin "AA4") (pinfunction "PL63A_AA4") (pintype "bidirectional"))
    )
    (net (code "235") (name "/EXTEND_B46") (class "Default")
      (node (ref "U1") (pin "AA3") (pinfunction "PL60B_AA3") (pintype "bidirectional"))
    )
    (net (code "236") (name "/EXTEND_B47") (class "Default")
      (node (ref "U1") (pin "AB4") (pinfunction "PL68A/VREF1_6_AB4") (pintype "bidirectional"))
    )
    (net (code "237") (name "/EXTEND_B48") (class "Default")
      (node (ref "U1") (pin "AC3") (pinfunction "PL64B_AC3") (pintype "bidirectional"))
    )
    (net (code "238") (name "/EXTEND_B49") (class "Default")
      (node (ref "U1") (pin "AD3") (pinfunction "PL66A_AD3") (pintype "bidirectional"))
    )
    (net (code "240") (name "/EXTEND_C0") (class "Default")
      (node (ref "U1") (pin "G20") (pinfunction "PT65B_G20") (pintype "bidirectional"))
    )
    (net (code "241") (name "/EXTEND_C1") (class "Default")
      (node (ref "U1") (pin "G24") (pinfunction "PR12B_G24") (pintype "bidirectional"))
    )
    (net (code "242") (name "/EXTEND_C2") (class "Default")
      (node (ref "U1") (pin "G19") (pinfunction "PT54B_G19") (pintype "bidirectional"))
    )
    (net (code "243") (name "/EXTEND_C3") (class "Default")
      (node (ref "U1") (pin "F23") (pinfunction "PR9A_F23") (pintype "bidirectional"))
    )
    (net (code "244") (name "/EXTEND_C4") (class "Default")
      (node (ref "U1") (pin "J21") (pinfunction "PR22B_J21") (pintype "bidirectional"))
    )
    (net (code "245") (name "/EXTEND_C5") (class "Default")
      (node (ref "U1") (pin "H22") (pinfunction "PR21A_H22") (pintype "bidirectional"))
    )
    (net (code "246") (name "/EXTEND_C6") (class "Default")
      (node (ref "U1") (pin "G21") (pinfunction "PR15A_G21") (pintype "bidirectional"))
    )
    (net (code "247") (name "/EXTEND_C7") (class "Default")
      (node (ref "U1") (pin "F22") (pinfunction "PR7A_F22") (pintype "bidirectional"))
    )
    (net (code "248") (name "/EXTEND_C8") (class "Default")
      (node (ref "U1") (pin "E23") (pinfunction "PR2B/VREF1_2_E23") (pintype "bidirectional"))
    )
    (net (code "249") (name "/EXTEND_C9") (class "Default")
      (node (ref "U1") (pin "D24") (pinfunction "PR8A_D24") (pintype "bidirectional"))
    )
    (net (code "250") (name "/EXTEND_C10") (class "Default")
      (node (ref "U1") (pin "D23") (pinfunction "PR2A/VREF2_2_D23") (pintype "bidirectional"))
    )
    (net (code "251") (name "/EXTEND_C11") (class "Default")
      (node (ref "U1") (pin "C24") (pinfunction "PT62A/TDQS62_C24") (pintype "bidirectional"))
    )
    (net (code "252") (name "/EXTEND_C12") (class "Default")
      (node (ref "U1") (pin "C25") (pinfunction "PR11A_C25") (pintype "bidirectional"))
    )
    (net (code "253") (name "/EXTEND_C13") (class "Default")
      (node (ref "U1") (pin "B26") (pinfunction "PT59B_B26") (pintype "bidirectional"))
    )
    (net (code "254") (name "/EXTEND_C14") (class "Default")
      (node (ref "U1") (pin "C22") (pinfunction "PT63A_C22") (pintype "bidirectional"))
    )
    (net (code "255") (name "/EXTEND_C15") (class "Default")
      (node (ref "U1") (pin "A24") (pinfunction "PT57B_A24") (pintype "bidirectional"))
    )
    (net (code "256") (name "/EXTEND_C16") (class "Default")
      (node (ref "U1") (pin "D21") (pinfunction "PT64B_D21") (pintype "bidirectional"))
    )
    (net (code "257") (name "/EXTEND_C17") (class "Default")
      (node (ref "U1") (pin "C21") (pinfunction "PT64A_C21") (pintype "bidirectional"))
    )
    (net (code "258") (name "/EXTEND_C18") (class "Default")
      (node (ref "U1") (pin "D20") (pinfunction "PT61B_D20") (pintype "bidirectional"))
    )
    (net (code "259") (name "/EXTEND_C19") (class "Default")
      (node (ref "U1") (pin "D19") (pinfunction "PT56A_D19") (pintype "bidirectional"))
    )
    (net (code "260") (name "/EXTEND_C20") (class "Default")
      (node (ref "U1") (pin "C19") (pinfunction "PT58A_C19") (pintype "bidirectional"))
    )
    (net (code "261") (name "/EXTEND_C21") (class "Default")
      (node (ref "U1") (pin "D18") (pinfunction "PT53B_D18") (pintype "bidirectional"))
    )
    (net (code "262") (name "/EXTEND_C22") (class "Default")
      (node (ref "U1") (pin "D17") (pinfunction "PT49A_D17") (pintype "bidirectional"))
    )
    (net (code "263") (name "/EXTEND_C23") (class "Default")
      (node (ref "U1") (pin "C17") (pinfunction "PT49B_C17") (pintype "bidirectional"))
    )
    (net (code "264") (name "/EXTEND_C24") (class "Default")
      (node (ref "U1") (pin "D16") (pinfunction "PT44B_D16") (pintype "bidirectional"))
    )
    (net (code "265") (name "/EXTEND_C25") (class "Default")
      (node (ref "U1") (pin "C16") (pinfunction "PT44A_C16") (pintype "bidirectional"))
    )
    (net (code "266") (name "/EXTEND_C26") (class "Default")
      (node (ref "U1") (pin "E15") (pinfunction "PT39B_E15") (pintype "bidirectional"))
    )
    (net (code "267") (name "/EXTEND_C27") (class "Default")
      (node (ref "U1") (pin "C15") (pinfunction "PT39A_C15") (pintype "bidirectional"))
    )
    (net (code "268") (name "/EXTEND_C28") (class "Default")
      (node (ref "U1") (pin "D15") (pinfunction "PT40B_D15") (pintype "bidirectional"))
    )
    (net (code "269") (name "/EXTEND_C29") (class "Default")
      (node (ref "U1") (pin "D14") (pinfunction "PT35B/VREF2_1_D14") (pintype "bidirectional"))
    )
    (net (code "270") (name "/EXTEND_C30") (class "Default")
      (node (ref "U1") (pin "D12") (pinfunction "PT27B_D12") (pintype "bidirectional"))
    )
    (net (code "271") (name "/EXTEND_C31") (class "Default")
      (node (ref "U1") (pin "C12") (pinfunction "PT27A_C12") (pintype "bidirectional"))
    )
    (net (code "272") (name "/EXTEND_C32") (class "Default")
      (node (ref "U1") (pin "E12") (pinfunction "PT24B_E12") (pintype "bidirectional"))
    )
    (net (code "273") (name "/EXTEND_C33") (class "Default")
      (node (ref "U1") (pin "C11") (pinfunction "PT22A/TDQS22_C11") (pintype "bidirectional"))
    )
    (net (code "274") (name "/EXTEND_C34") (class "Default")
      (node (ref "U1") (pin "D11") (pinfunction "PT22B_D11") (pintype "bidirectional"))
    )
    (net (code "275") (name "/EXTEND_C35") (class "Default")
      (node (ref "U1") (pin "C10") (pinfunction "PT17B_C10") (pintype "bidirectional"))
    )
    (net (code "276") (name "/EXTEND_C36") (class "Default")
      (node (ref "U1") (pin "D10") (pinfunction "PT17A_D10") (pintype "bidirectional"))
    )
    (net (code "277") (name "/EXTEND_C37") (class "Default")
      (node (ref "U1") (pin "C8") (pinfunction "PT11A_C8") (pintype "bidirectional"))
    )
    (net (code "278") (name "/EXTEND_C38") (class "Default")
      (node (ref "U1") (pin "D8") (pinfunction "PT6B_D8") (pintype "bidirectional"))
    )
    (net (code "279") (name "/EXTEND_C39") (class "Default")
      (node (ref "U1") (pin "C6") (pinfunction "PT18A_C6") (pintype "bidirectional"))
    )
    (net (code "280") (name "/EXTEND_C40") (class "Default")
      (node (ref "U1") (pin "B9") (pinfunction "PT24A_B9") (pintype "bidirectional"))
    )
    (net (code "281") (name "/EXTEND_C41") (class "Default")
      (node (ref "U1") (pin "D6") (pinfunction "PT3A_D6") (pintype "bidirectional"))
    )
    (net (code "282") (name "/EXTEND_C42") (class "Default")
      (node (ref "U1") (pin "B7") (pinfunction "PT21A_B7") (pintype "bidirectional"))
    )
    (net (code "283") (name "/EXTEND_C43") (class "Default")
      (node (ref "U1") (pin "C5") (pinfunction "PT5A_C5") (pintype "bidirectional"))
    )
    (net (code "284") (name "/EXTEND_C44") (class "Default")
      (node (ref "U1") (pin "A6") (pinfunction "PT16A_A6") (pintype "bidirectional"))
    )
    (net (code "285") (name "/EXTEND_C45") (class "Default")
      (node (ref "U1") (pin "D5") (pinfunction "PL6B_D5") (pintype "bidirectional"))
    )
    (net (code "286") (name "/EXTEND_C46") (class "Default")
      (node (ref "U1") (pin "A5") (pinfunction "PT13B_A5") (pintype "bidirectional"))
    )
    (net (code "287") (name "/EXTEND_C47") (class "Default")
      (node (ref "U1") (pin "C4") (pinfunction "PT5B_C4") (pintype "bidirectional"))
    )
    (net (code "288") (name "/EXTEND_C48") (class "Default")
      (node (ref "U1") (pin "B5") (pinfunction "PT10A_B5") (pintype "bidirectional"))
    )
    (net (code "289") (name "/EXTEND_C49") (class "Default")
      (node (ref "U1") (pin "A4") (pinfunction "PT13A_A4") (pintype "bidirectional"))
    )
    (net (code "291") (name "/FPGA_CCLK") (class "Default")
      (node (ref "R26") (pin "1") (pinfunction "1_1") (pintype "passive"))
      (node (ref "R7") (pin "1") (pinfunction "1_1") (pintype "passive"))
    )
    (net (code "292") (name "/FPGA_CLK") (class "Default")
      (node (ref "U1") (pin "AF14") (pinfunction "PB33A/PCLKT5_0_AF14") (pintype "bidirectional"))
    )
    (net (code "293") (name "/FPGA_CLK1") (class "Default")
      (node (ref "U1") (pin "K26") (pinfunction "PR34A/PCLKT2_0_K26") (pintype "bidirectional"))
    )
    (net (code "294") (name "/FPGA_DIN") (class "Default")
      (node (ref "R27") (pin "1") (pinfunction "1_1") (pintype "passive"))
    )
    (net (code "295") (name "/FPGA_DONE") (class "Default")
      (node (ref "NT6") (pin "2") (pinfunction "Net2_2") (pintype "passive"))
      (node (ref "R25") (pin "1") (pinfunction "1_1") (pintype "passive"))
      (node (ref "R4") (pin "1") (pinfunction "1_1") (pintype "passive"))
    )
    (net (code "296") (name "/FPGA_ID0") (class "Default")
      (node (ref "NT2") (pin "1") (pinfunction "Net1_1") (pintype "passive"))
    )
    (net (code "297") (name "/FPGA_ID1") (class "Default")
      (node (ref "NT3") (pin "1") (pinfunction "Net1_1") (pintype "passive"))
    )
    (net (code "298") (name "/FPGA_ID2") (class "Default")
      (node (ref "NT4") (pin "1") (pinfunction "Net1_1") (pintype "passive"))
    )
    (net (code "299") (name "/FPGA_ID3") (class "Default")
      (node (ref "NT5") (pin "1") (pinfunction "Net1_1") (pintype "passive"))
    )
    (net (code "300") (name "/FPGA_INIT") (class "Default")
      (node (ref "R3") (pin "1") (pinfunction "1_1") (pintype "passive"))
      (node (ref "R8") (pin "1") (pinfunction "1_1") (pintype "passive"))
    )
    (net (code "301") (name "/FPGA_M0") (class "Default")
      (node (ref "R23") (pin "1") (pinfunction "1_1") (pintype "passive"))
    )
    (net (code "302") (name "/FPGA_M1") (class "Default")
      (node (ref "R18") (pin "1") (pinfunction "1_1") (pintype "passive"))
    )
    (net (code "303") (name "/FPGA_M2") (class "Default")
      (node (ref "R28") (pin "1") (pinfunction "1_1") (pintype "passive"))
    )
    (net (code "305") (name "/FPGA_PROGRAM") (class "Default")
      (node (ref "R1") (pin "1") (pinfunction "1_1") (pintype "passive"))
      (node (ref "R24") (pin "1") (pinfunction "1_1") (pintype "passive"))
    )
    (net (code "308") (name "/FPGA_TCK") (class "Default")
      (node (ref "R14") (pin "1") (pinfunction "1_1") (pintype "passive"))
    )
    (net (code "309") (name "/FPGA_TDI") (class "Default")
      (node (ref "R20") (pin "1") (pinfunction "1_1") (pintype "passive"))
    )
    (net (code "310") (name "/FPGA_TDO") (class "Default")
      (node (ref "R2") (pin "1") (pinfunction "1_1") (pintype "passive"))
      (node (ref "R22") (pin "1") (pinfunction "1_1") (pintype "passive"))
    )
    (net (code "311") (name "/FPGA_TMS") (class "Default")
      (node (ref "R12") (pin "1") (pinfunction "1_1") (pintype "passive"))
    )
    (net (code "312") (name "/INITN") (class "Default")
      (node (ref "R8") (pin "2") (pinfunction "2_2") (pintype "passive"))
    )
    (net (code "313") (name "/IO0") (class "Default")
      (node (ref "U1") (pin "AF2") (pinfunction "PB8A_AF2") (pintype "bidirectional"))
    )
    (net (code "314") (name "/IO1") (class "Default")
      (node (ref "U1") (pin "AE3") (pinfunction "PB11A_AE3") (pintype "bidirectional"))
    )
    (net (code "315") (name "/IO2") (class "Default")
      (node (ref "U1") (pin "AF3") (pinfunction "PB12A_AF3") (pintype "bidirectional"))
    )
    (net (code "316") (name "/IO3") (class "Default")
      (node (ref "U1") (pin "AE4") (pinfunction "PB13A_AE4") (pintype "bidirectional"))
    )
    (net (code "317") (name "/IO4") (class "Default")
      (node (ref "U1") (pin "AF4") (pinfunction "PB13B_AF4") (pintype "bidirectional"))
    )
    (net (code "318") (name "/IO5") (class "Default")
      (node (ref "U1") (pin "AE5") (pinfunction "PB14A/BDQS14_AE5") (pintype "bidirectional"))
    )
    (net (code "319") (name "/IO6") (class "Default")
      (node (ref "U1") (pin "AF5") (pinfunction "PB15A_AF5") (pintype "bidirectional"))
    )
    (net (code "320") (name "/IO7") (class "Default")
      (node (ref "U1") (pin "AE6") (pinfunction "PB17B_AE6") (pintype "bidirectional"))
    )
    (net (code "321") (name "/IO8") (class "Default")
      (node (ref "U1") (pin "AF6") (pinfunction "PB17A_AF6") (pintype "bidirectional"))
    )
    (net (code "322") (name "/IO9") (class "Default")
      (node (ref "U1") (pin "AE7") (pinfunction "PB19A_AE7") (pintype "bidirectional"))
    )
    (net (code "323") (name "/IO10") (class "Default")
      (node (ref "U1") (pin "AF7") (pinfunction "PB18A_AF7") (pintype "bidirectional"))
    )
    (net (code "324") (name "/IO11") (class "Default")
      (node (ref "U1") (pin "AE8") (pinfunction "PB23A_AE8") (pintype "bidirectional"))
    )
    (net (code "325") (name "/IO12") (class "Default")
      (node (ref "U1") (pin "AF8") (pinfunction "PB21A_AF8") (pintype "bidirectional"))
    )
    (net (code "326") (name "/IO13") (class "Default")
      (node (ref "U1") (pin "AE9") (pinfunction "PB25B_AE9") (pintype "bidirectional"))
    )
    (net (code "327") (name "/IO14") (class "Default")
      (node (ref "U1") (pin "AF9") (pinfunction "PB21B_AF9") (pintype "bidirectional"))
    )
    (net (code "328") (name "/IO15") (class "Default")
      (node (ref "U1") (pin "AE10") (pinfunction "PB25A_AE10") (pintype "bidirectional"))
    )
    (net (code "329") (name "/IO16") (class "Default")
      (node (ref "U1") (pin "AF10") (pinfunction "PB24A_AF10") (pintype "bidirectional"))
    )
    (net (code "330") (name "/IO17") (class "Default")
      (node (ref "U1") (pin "AE11") (pinfunction "PB27A_AE11") (pintype "bidirectional"))
    )
    (net (code "331") (name "/IO18") (class "Default")
      (node (ref "U1") (pin "AF11") (pinfunction "PB27B_AF11") (pintype "bidirectional"))
    )
    (net (code "332") (name "/IO19") (class "Default")
      (node (ref "U1") (pin "AE12") (pinfunction "PB28B_AE12") (pintype "bidirectional"))
    )
    (net (code "333") (name "/IO20") (class "Default")
      (node (ref "U1") (pin "AF12") (pinfunction "PB28A_AF12") (pintype "bidirectional"))
    )
    (net (code "334") (name "/IO21") (class "Default")
      (node (ref "U1") (pin "AF13") (pinfunction "PB31B_AF13") (pintype "bidirectional"))
    )
    (net (code "335") (name "/IO22") (class "Default")
      (node (ref "U1") (pin "AF16") (pinfunction "PB39A_AF16") (pintype "bidirectional"))
    )
    (net (code "336") (name "/IO23") (class "Default")
      (node (ref "U1") (pin "AE16") (pinfunction "PB40A_AE16") (pintype "bidirectional"))
    )
    (net (code "337") (name "/IO24") (class "Default")
      (node (ref "U1") (pin "AF17") (pinfunction "PB41A_AF17") (pintype "bidirectional"))
    )
    (net (code "338") (name "/IO25") (class "Default")
      (node (ref "U1") (pin "AE17") (pinfunction "PB41B/D6/SPID1_AE17") (pintype "bidirectional"))
    )
    (net (code "339") (name "/IO26") (class "Default")
      (node (ref "U1") (pin "AF18") (pinfunction "PB45B_AF18") (pintype "bidirectional"))
    )
    (net (code "340") (name "/IO27") (class "Default")
      (node (ref "U1") (pin "AE18") (pinfunction "PB45A_AE18") (pintype "bidirectional"))
    )
    (net (code "341") (name "/IO28") (class "Default")
      (node (ref "U1") (pin "AF19") (pinfunction "PB47A_AF19") (pintype "bidirectional"))
    )
    (net (code "342") (name "/IO29") (class "Default")
      (node (ref "U1") (pin "AE19") (pinfunction "PB53A_AE19") (pintype "bidirectional"))
    )
    (net (code "343") (name "/IO30") (class "Default")
      (node (ref "U1") (pin "AF20") (pinfunction "PB49B_AF20") (pintype "bidirectional"))
    )
    (net (code "344") (name "/IO31") (class "Default")
      (node (ref "U1") (pin "AE20") (pinfunction "PB53B_AE20") (pintype "bidirectional"))
    )
    (net (code "345") (name "/IO32") (class "Default")
      (node (ref "U1") (pin "AE21") (pinfunction "PB50A_AE21") (pintype "bidirectional"))
    )
    (net (code "346") (name "/IO33") (class "Default")
      (node (ref "U1") (pin "AE22") (pinfunction "PB52A_AE22") (pintype "bidirectional"))
    )
    (net (code "347") (name "/IO34") (class "Default")
      (node (ref "U1") (pin "AE23") (pinfunction "PB57B_AE23") (pintype "bidirectional"))
    )
    (net (code "348") (name "/IO35") (class "Default")
      (node (ref "U1") (pin "AE24") (pinfunction "PB63A_AE24") (pintype "bidirectional"))
    )
    (net (code "350") (name "/KBCLOCK") (class "Default")
      (node (ref "U1") (pin "B15") (pinfunction "PT37B_B15") (pintype "bidirectional"))
    )
    (net (code "351") (name "/KBDATA") (class "Default")
      (node (ref "U1") (pin "A15") (pinfunction "PT37A_A15") (pintype "bidirectional"))
    )
    (net (code "352") (name "/LED0") (class "Default")
      (node (ref "U1") (pin "AC6") (pinfunction "PB5A_AC6") (pintype "bidirectional"))
    )
    (net (code "353") (name "/LED1") (class "Default")
      (node (ref "U1") (pin "AD6") (pinfunction "PB16A_AD6") (pintype "bidirectional"))
    )
    (net (code "354") (name "/LED2") (class "Default")
      (node (ref "U1") (pin "AC7") (pinfunction "PB3A_AC7") (pintype "bidirectional"))
    )
    (net (code "355") (name "/LED3") (class "Default")
      (node (ref "U1") (pin "AC8") (pinfunction "PB6B_AC8") (pintype "bidirectional"))
    )
    (net (code "356") (name "/LED4") (class "Default")
      (node (ref "U1") (pin "AD8") (pinfunction "PB10A_AD8") (pintype "bidirectional"))
    )
    (net (code "357") (name "/LED5") (class "Default")
      (node (ref "U1") (pin "AC10") (pinfunction "PB16B_AC10") (pintype "bidirectional"))
    )
    (net (code "358") (name "/LED6") (class "Default")
      (node (ref "U1") (pin "AD10") (pinfunction "PB19B_AD10") (pintype "bidirectional"))
    )
    (net (code "359") (name "/LED7") (class "Default")
      (node (ref "U1") (pin "AC11") (pinfunction "PB23B_AC11") (pintype "bidirectional"))
    )
    (net (code "360") (name "/M0") (class "Default")
      (node (ref "R23") (pin "2") (pinfunction "2_2") (pintype "passive"))
    )
    (net (code "361") (name "/M1") (class "Default")
      (node (ref "R18") (pin "2") (pinfunction "2_2") (pintype "passive"))
    )
    (net (code "362") (name "/M2") (class "Default")
      (node (ref "R28") (pin "2") (pinfunction "2_2") (pintype "passive"))
    )
    (net (code "364") (name "/MOUSECLOCK") (class "Default")
      (node (ref "U1") (pin "A16") (pinfunction "PT41A_A16") (pintype "bidirectional"))
    )
    (net (code "365") (name "/MOUSEDATA") (class "Default")
      (node (ref "U1") (pin "B16") (pinfunction "PT40A_B16") (pintype "bidirectional"))
    )
    (net (code "366") (name "/NEXUS_TCK") (class "Default")
      (node (ref "U1") (pin "K21") (pinfunction "PR25B_K21") (pintype "bidirectional"))
    )
    (net (code "367") (name "/NEXUS_TDI") (class "Default")
      (node (ref "U1") (pin "L21") (pinfunction "PR31A/RDQS31_L21") (pintype "bidirectional"))
    )
    (net (code "368") (name "/NEXUS_TDO") (class "Default")
      (node (ref "U1") (pin "B25") (pinfunction "PT60B_B25") (pintype "bidirectional"))
    )
    (net (code "369") (name "/NEXUS_TMS") (class "Default")
      (node (ref "U1") (pin "J20") (pinfunction "PR24A_J20") (pintype "bidirectional"))
    )
    (net (code "371") (name "/ONE_WIRE_DB_PB") (class "Default")
      (node (ref "U1") (pin "AB11") (pinfunction "PB24B_AB11") (pintype "bidirectional"))
    )
    (net (code "374") (name "/PROGRAMN") (class "Default")
      (node (ref "R24") (pin "2") (pinfunction "2_2") (pintype "passive"))
    )
    (net (code "376") (name "/REF_CLK") (class "Default")
      (node (ref "U1") (pin "AE14") (pinfunction "PB33B/PCLKC5_0_AE14") (pintype "bidirectional"))
    )
    (net (code "377") (name "/RS232_CTS") (class "Default")
      (node (ref "U1") (pin "A11") (pinfunction "PT28B_A11") (pintype "bidirectional"))
    )
    (net (code "378") (name "/RS232_RTS") (class "Default")
      (node (ref "U1") (pin "A10") (pinfunction "PT26A_A10") (pintype "bidirectional"))
    )
    (net (code "379") (name "/RS232_RX") (class "Default")
      (node (ref "U1") (pin "B12") (pinfunction "PT29A_B12") (pintype "bidirectional"))
    )
    (net (code "380") (name "/RS232_TX") (class "Default")
      (node (ref "U1") (pin "B11") (pinfunction "PT28A_B11") (pintype "bidirectional"))
    )
    (net (code "381") (name "/SCL") (class "Default")
      (node (ref "U1") (pin "AA10") (pinfunction "PB20B_AA10") (pintype "bidirectional"))
    )
    (net (code "382") (name "/SDA") (class "Default")
      (node (ref "U1") (pin "AD9") (pinfunction "PB12B_AD9") (pintype "bidirectional"))
    )
    (net (code "383") (name "/SPI_CLK") (class "Default")
      (node (ref "U1") (pin "F14") (pinfunction "PT34B_F14") (pintype "bidirectional"))
    )
    (net (code "384") (name "/SPI_DIN") (class "Default")
      (node (ref "U1") (pin "F13") (pinfunction "PT30B_F13") (pintype "bidirectional"))
    )
    (net (code "385") (name "/SPI_DOUT") (class "Default")
      (node (ref "U1") (pin "F16") (pinfunction "PT43B_F16") (pintype "bidirectional"))
    )
    (net (code "386") (name "/SPI_MODE") (class "Default")
      (node (ref "U1") (pin "F17") (pinfunction "PT48B_F17") (pintype "bidirectional"))
    )
    (net (code "387") (name "/SPI_SEL") (class "Default")
      (node (ref "U1") (pin "F15") (pinfunction "PT38B_F15") (pintype "bidirectional"))
    )
    (net (code "388") (name "/SRAM1_A0") (class "Default")
      (node (ref "U1") (pin "AD21") (pinfunction "PB60A_AD21") (pintype "bidirectional"))
    )
    (net (code "389") (name "/SRAM1_A1") (class "Default")
      (node (ref "U1") (pin "AD22") (pinfunction "PB64A_AD22") (pintype "bidirectional"))
    )
    (net (code "390") (name "/SRAM1_A2") (class "Default")
      (node (ref "U1") (pin "AD23") (pinfunction "PB63B_AD23") (pintype "bidirectional"))
    )
    (net (code "391") (name "/SRAM1_A3") (class "Default")
      (node (ref "U1") (pin "AD24") (pinfunction "PR67B_AD24") (pintype "bidirectional"))
    )
    (net (code "392") (name "/SRAM1_A4") (class "Default")
      (node (ref "U1") (pin "AC24") (pinfunction "PR68A/VREF1_3_AC24") (pintype "bidirectional"))
    )
    (net (code "393") (name "/SRAM1_A5") (class "Default")
      (node (ref "U1") (pin "AA22") (pinfunction "PR64A_AA22") (pintype "bidirectional"))
    )
    (net (code "394") (name "/SRAM1_A6") (class "Default")
      (node (ref "U1") (pin "AA21") (pinfunction "PR62A_AA21") (pintype "bidirectional"))
    )
    (net (code "395") (name "/SRAM1_A7") (class "Default")
      (node (ref "U1") (pin "W22") (pinfunction "PR55B/RLM0_PLLC_FB_A_W22") (pintype "bidirectional"))
    )
    (net (code "396") (name "/SRAM1_A8") (class "Default")
      (node (ref "U1") (pin "R21") (pinfunction "PR42B_R21") (pintype "bidirectional"))
    )
    (net (code "397") (name "/SRAM1_A9") (class "Default")
      (node (ref "U1") (pin "N23") (pinfunction "PR37B_N23") (pintype "bidirectional"))
    )
    (net (code "398") (name "/SRAM1_A10") (class "Default")
      (node (ref "U1") (pin "T21") (pinfunction "PR48A/RDQS48_T21") (pintype "bidirectional"))
    )
    (net (code "399") (name "/SRAM1_A11") (class "Default")
      (node (ref "U1") (pin "U21") (pinfunction "PR48B_U21") (pintype "bidirectional"))
    )
    (net (code "400") (name "/SRAM1_A12") (class "Default")
      (node (ref "U1") (pin "Y19") (pinfunction "PR65A/RDQS65_Y19") (pintype "bidirectional"))
    )
    (net (code "401") (name "/SRAM1_A13") (class "Default")
      (node (ref "U1") (pin "Y20") (pinfunction "PR65B_Y20") (pintype "bidirectional"))
    )
    (net (code "402") (name "/SRAM1_A14") (class "Default")
      (node (ref "U1") (pin "Y21") (pinfunction "PR62B_Y21") (pintype "bidirectional"))
    )
    (net (code "403") (name "/SRAM1_A15") (class "Default")
      (node (ref "U1") (pin "AC20") (pinfunction "PB60B_AC20") (pintype "bidirectional"))
    )
    (net (code "404") (name "/SRAM1_A16") (class "Default")
      (node (ref "U1") (pin "AD20") (pinfunction "PB58B_AD20") (pintype "bidirectional"))
    )
    (net (code "405") (name "/SRAM1_A17") (class "Default")
      (node (ref "U1") (pin "AC19") (pinfunction "PB59A_AC19") (pintype "bidirectional"))
    )
    (net (code "406") (name "/SRAM1_A18") (class "Default")
      (node (ref "U1") (pin "AB22") (pinfunction "PB65B_AB22") (pintype "bidirectional"))
    )
    (net (code "408") (name "/SRAM1_D0") (class "Default")
      (node (ref "U1") (pin "AA15") (pinfunction "PB42B_AA15") (pintype "bidirectional"))
    )
    (net (code "409") (name "/SRAM1_D1") (class "Default")
      (node (ref "U1") (pin "AA16") (pinfunction "PB47B_AA16") (pintype "bidirectional"))
    )
    (net (code "410") (name "/SRAM1_D2") (class "Default")
      (node (ref "U1") (pin "AA17") (pinfunction "PB48A_AA17") (pintype "bidirectional"))
    )
    (net (code "411") (name "/SRAM1_D3") (class "Default")
      (node (ref "U1") (pin "AB18") (pinfunction "PB56B_AB18") (pintype "bidirectional"))
    )
    (net (code "412") (name "/SRAM1_D4") (class "Default")
      (node (ref "U1") (pin "AB21") (pinfunction "PB62A/BDQS62_AB21") (pintype "bidirectional"))
    )
    (net (code "413") (name "/SRAM1_D5") (class "Default")
      (node (ref "U1") (pin "AB20") (pinfunction "PB62B_AB20") (pintype "bidirectional"))
    )
    (net (code "414") (name "/SRAM1_D6") (class "Default")
      (node (ref "U1") (pin "Y22") (pinfunction "PR61A_Y22") (pintype "bidirectional"))
    )
    (net (code "415") (name "/SRAM1_D7") (class "Default")
      (node (ref "U1") (pin "W21") (pinfunction "PR55A/RLM0_PLLT_FB_A_W21") (pintype "bidirectional"))
    )
    (net (code "416") (name "/SRAM1_D8") (class "Default")
      (node (ref "U1") (pin "AA20") (pinfunction "PB55B_AA20") (pintype "bidirectional"))
    )
    (net (code "417") (name "/SRAM1_D9") (class "Default")
      (node (ref "U1") (pin "AB19") (pinfunction "PB59B_AB19") (pintype "bidirectional"))
    )
    (net (code "418") (name "/SRAM1_D10") (class "Default")
      (node (ref "U1") (pin "AA18") (pinfunction "PB52B_AA18") (pintype "bidirectional"))
    )
    (net (code "419") (name "/SRAM1_D11") (class "Default")
      (node (ref "U1") (pin "AB23") (pinfunction "PR63B_AB23") (pintype "bidirectional"))
    )
    (net (code "420") (name "/SRAM1_D12") (class "Default")
      (node (ref "U1") (pin "AC23") (pinfunction "PR68B/VREF2_3_AC23") (pintype "bidirectional"))
    )
    (net (code "421") (name "/SRAM1_D13") (class "Default")
      (node (ref "U1") (pin "AC22") (pinfunction "PB65A_AC22") (pintype "bidirectional"))
    )
    (net (code "422") (name "/SRAM1_D14") (class "Default")
      (node (ref "U1") (pin "AC21") (pinfunction "PB64B_AC21") (pintype "bidirectional"))
    )
    (net (code "423") (name "/SRAM1_D15") (class "Default")
      (node (ref "U1") (pin "AD17") (pinfunction "PB43A_AD17") (pintype "bidirectional"))
    )
    (net (code "424") (name "/SRAM1_NBHE") (class "Default")
      (node (ref "U1") (pin "AC18") (pinfunction "PB56A_AC18") (pintype "bidirectional"))
    )
    (net (code "425") (name "/SRAM1_NBLE") (class "Default")
      (node (ref "U1") (pin "AC17") (pinfunction "PB50B_AC17") (pintype "bidirectional"))
    )
    (net (code "426") (name "/SRAM1_NCS") (class "Default")
      (node (ref "U1") (pin "AA14") (pinfunction "PB35B/CSN_AA14") (pintype "bidirectional"))
    )
    (net (code "427") (name "/SRAM1_NOE") (class "Default")
      (node (ref "U1") (pin "AD19") (pinfunction "PB58A_AD19") (pintype "bidirectional"))
    )
    (net (code "428") (name "/SRAM1_NWE") (class "Default")
      (node (ref "U1") (pin "AA19") (pinfunction "PB54A/BDQS54_AA19") (pintype "bidirectional"))
    )
    (net (code "430") (name "/SRAM2_A0") (class "Default")
      (node (ref "U1") (pin "U22") (pinfunction "PR49A_U22") (pintype "bidirectional"))
    )
    (net (code "431") (name "/SRAM2_A1") (class "Default")
      (node (ref "U1") (pin "R22") (pinfunction "PR42A_R22") (pintype "bidirectional"))
    )
    (net (code "432") (name "/SRAM2_A2") (class "Default")
      (node (ref "U1") (pin "P22") (pinfunction "PR40A/RDQS40_P22") (pintype "bidirectional"))
    )
    (net (code "433") (name "/SRAM2_A3") (class "Default")
      (node (ref "U1") (pin "P21") (pinfunction "PR38A_P21") (pintype "bidirectional"))
    )
    (net (code "434") (name "/SRAM2_A4") (class "Default")
      (node (ref "U1") (pin "AB24") (pinfunction "PR63A_AB24") (pintype "bidirectional"))
    )
    (net (code "435") (name "/SRAM2_A5") (class "Default")
      (node (ref "U1") (pin "T22") (pinfunction "PR46B_T22") (pintype "bidirectional"))
    )
    (net (code "436") (name "/SRAM2_A6") (class "Default")
      (node (ref "U1") (pin "R24") (pinfunction "PR44A_R24") (pintype "bidirectional"))
    )
    (net (code "437") (name "/SRAM2_A7") (class "Default")
      (node (ref "U1") (pin "R23") (pinfunction "PR45A_R23") (pintype "bidirectional"))
    )
    (net (code "438") (name "/SRAM2_A8") (class "Default")
      (node (ref "U1") (pin "P24") (pinfunction "PR41A_P24") (pintype "bidirectional"))
    )
    (net (code "439") (name "/SRAM2_A9") (class "Default")
      (node (ref "U1") (pin "P23") (pinfunction "PR40B_P23") (pintype "bidirectional"))
    )
    (net (code "440") (name "/SRAM2_A10") (class "Default")
      (node (ref "U1") (pin "P26") (pinfunction "PR43A_P26") (pintype "bidirectional"))
    )
    (net (code "441") (name "/SRAM2_A11") (class "Default")
      (node (ref "U1") (pin "R26") (pinfunction "PR43B_R26") (pintype "bidirectional"))
    )
    (net (code "442") (name "/SRAM2_A12") (class "Default")
      (node (ref "U1") (pin "R25") (pinfunction "PR44B_R25") (pintype "bidirectional"))
    )
    (net (code "443") (name "/SRAM2_A13") (class "Default")
      (node (ref "U1") (pin "T26") (pinfunction "PR47A_T26") (pintype "bidirectional"))
    )
    (net (code "444") (name "/SRAM2_A14") (class "Default")
      (node (ref "U1") (pin "T25") (pinfunction "PR47B_T25") (pintype "bidirectional"))
    )
    (net (code "445") (name "/SRAM2_A15") (class "Default")
      (node (ref "U1") (pin "AD26") (pinfunction "PR66A_AD26") (pintype "bidirectional"))
    )
    (net (code "446") (name "/SRAM2_A16") (class "Default")
      (node (ref "U1") (pin "AD25") (pinfunction "PR67A_AD25") (pintype "bidirectional"))
    )
    (net (code "447") (name "/SRAM2_A17") (class "Default")
      (node (ref "U1") (pin "AE26") (pinfunction "PR66B_AE26") (pintype "bidirectional"))
    )
    (net (code "448") (name "/SRAM2_A18") (class "Default")
      (node (ref "U1") (pin "U26") (pinfunction "PR51A_U26") (pintype "bidirectional"))
    )
    (net (code "450") (name "/SRAM2_D0") (class "Default")
      (node (ref "U1") (pin "AA24") (pinfunction "PR60B_AA24") (pintype "bidirectional"))
    )
    (net (code "451") (name "/SRAM2_D1") (class "Default")
      (node (ref "U1") (pin "Y23") (pinfunction "PR61B_Y23") (pintype "bidirectional"))
    )
    (net (code "452") (name "/SRAM2_D2") (class "Default")
      (node (ref "U1") (pin "Y24") (pinfunction "PR60A_Y24") (pintype "bidirectional"))
    )
    (net (code "453") (name "/SRAM2_D3") (class "Default")
      (node (ref "U1") (pin "W24") (pinfunction "PR56A/RLM0_PLLT_IN_A_W24") (pintype "bidirectional"))
    )
    (net (code "454") (name "/SRAM2_D4") (class "Default")
      (node (ref "U1") (pin "W23") (pinfunction "PR56B/RLM0_PLLC_IN_A_W23") (pintype "bidirectional"))
    )
    (net (code "455") (name "/SRAM2_D5") (class "Default")
      (node (ref "U1") (pin "U23") (pinfunction "PR49B_U23") (pintype "bidirectional"))
    )
    (net (code "456") (name "/SRAM2_D6") (class "Default")
      (node (ref "U1") (pin "U24") (pinfunction "PR50B_U24") (pintype "bidirectional"))
    )
    (net (code "457") (name "/SRAM2_D7") (class "Default")
      (node (ref "U1") (pin "T23") (pinfunction "PR46A_T23") (pintype "bidirectional"))
    )
    (net (code "458") (name "/SRAM2_D8") (class "Default")
      (node (ref "U1") (pin "U25") (pinfunction "PR50A_U25") (pintype "bidirectional"))
    )
    (net (code "459") (name "/SRAM2_D9") (class "Default")
      (node (ref "U1") (pin "V26") (pinfunction "PR51B_V26") (pintype "bidirectional"))
    )
    (net (code "460") (name "/SRAM2_D10") (class "Default")
      (node (ref "U1") (pin "W26") (pinfunction "PR53A/D7/SPID0_W26") (pintype "bidirectional"))
    )
    (net (code "461") (name "/SRAM2_D11") (class "Default")
      (node (ref "U1") (pin "W25") (pinfunction "PR53B/BUSY/SISPI_W25") (pintype "bidirectional"))
    )
    (net (code "462") (name "/SRAM2_D12") (class "Default")
      (node (ref "U1") (pin "Y26") (pinfunction "PR54A/DOUT/CSON_Y26") (pintype "bidirectional"))
    )
    (net (code "463") (name "/SRAM2_D13") (class "Default")
      (node (ref "U1") (pin "AA26") (pinfunction "PR57A/RDQS57_AA26") (pintype "bidirectional"))
    )
    (net (code "464") (name "/SRAM2_D14") (class "Default")
      (node (ref "U1") (pin "AA25") (pinfunction "PR58A_AA25") (pintype "bidirectional"))
    )
    (net (code "465") (name "/SRAM2_D15") (class "Default")
      (node (ref "U1") (pin "AB26") (pinfunction "PR57B_AB26") (pintype "bidirectional"))
    )
    (net (code "466") (name "/SRAM2_NBHE") (class "Default")
      (node (ref "U1") (pin "AC26") (pinfunction "PR59A_AC26") (pintype "bidirectional"))
    )
    (net (code "467") (name "/SRAM2_NBLE") (class "Default")
      (node (ref "U1") (pin "AB25") (pinfunction "PR58B_AB25") (pintype "bidirectional"))
    )
    (net (code "468") (name "/SRAM2_NCS") (class "Default")
      (node (ref "U1") (pin "AA23") (pinfunction "PR64B_AA23") (pintype "bidirectional"))
    )
    (net (code "469") (name "/SRAM2_NOE") (class "Default")
      (node (ref "U1") (pin "AC25") (pinfunction "PR59B_AC25") (pintype "bidirectional"))
    )
    (net (code "470") (name "/SRAM2_NWE") (class "Default")
      (node (ref "U1") (pin "T24") (pinfunction "PR45B_T24") (pintype "bidirectional"))
    )
    (net (code "472") (name "/STATUS_LED") (class "Default")
      (node (ref "NT6") (pin "1") (pinfunction "Net1_1") (pintype "passive"))
    )
    (net (code "473") (name "/SW0") (class "Default")
      (node (ref "U1") (pin "AA11") (pinfunction "PB26A_AA11") (pintype "bidirectional"))
    )
    (net (code "474") (name "/SW1") (class "Default")
      (node (ref "U1") (pin "AB10") (pinfunction "PB18B_AB10") (pintype "bidirectional"))
    )
    (net (code "475") (name "/SW2") (class "Default")
      (node (ref "U1") (pin "AA9") (pinfunction "PB14B_AA9") (pintype "bidirectional"))
    )
    (net (code "476") (name "/SW3") (class "Default")
      (node (ref "U1") (pin "AB8") (pinfunction "PB6A/BDQS6_AB8") (pintype "bidirectional"))
    )
    (net (code "477") (name "/SW4") (class "Default")
      (node (ref "U1") (pin "AA7") (pinfunction "PB4B_AA7") (pintype "bidirectional"))
    )
    (net (code "479") (name "/TCK") (class "Default")
      (node (ref "R14") (pin "2") (pinfunction "2_2") (pintype "passive"))
    )
    (net (code "480") (name "/TDI") (class "Default")
      (node (ref "R20") (pin "2") (pinfunction "2_2") (pintype "passive"))
    )
    (net (code "481") (name "/TDO") (class "Default")
      (node (ref "R22") (pin "2") (pinfunction "2_2") (pintype "passive"))
    )
    (net (code "483") (name "/TMS") (class "Default")
      (node (ref "R12") (pin "2") (pinfunction "2_2") (pintype "passive"))
    )
    (net (code "484") (name "/UGCLK0") (class "Default")
      (node (ref "U1") (pin "B14") (pinfunction "PT33B/PCLKC0_0_B14") (pintype "bidirectional"))
    )
    (net (code "485") (name "/UGCLK1") (class "Default")
      (node (ref "U1") (pin "N1") (pinfunction "PL34B/PCLKC7_0_N1") (pintype "bidirectional"))
    )
    (net (code "486") (name "/UGCLK2") (class "Default")
      (node (ref "U1") (pin "N2") (pinfunction "PL34A/PCLKT7_0_N2") (pintype "bidirectional"))
    )
    (net (code "505") (name "3V3") (class "Default")
      (node (ref "NT2") (pin "2") (pinfunction "Net2_2") (pintype "passive"))
      (node (ref "NT3") (pin "2") (pinfunction "Net2_2") (pintype "passive"))
      (node (ref "R1") (pin "2") (pinfunction "2_2") (pintype "passive"))
      (node (ref "R2") (pin "2") (pinfunction "2_2") (pintype "passive"))
      (node (ref "R3") (pin "2") (pinfunction "2_2") (pintype "passive"))
      (node (ref "R4") (pin "2") (pinfunction "2_2") (pintype "passive"))
      (node (ref "R7") (pin "2") (pinfunction "2_2") (pintype "passive"))
    )
    (net (code "506") (name "GND") (class "Default")
      (node (ref "NT4") (pin "2") (pinfunction "Net2_2") (pintype "passive"))
      (node (ref "NT5") (pin "2") (pinfunction "Net2_2") (pintype "passive"))
    )
    (net (code "507") (name "unconnected-(U1A-PT2A-PadE6)") (class "Default")
      (node (ref "U1") (pin "E6") (pinfunction "PT2A_E6") (pintype "bidirectional"))
    )
    (net (code "508") (name "unconnected-(U1A-PT2B-PadD7)") (class "Default")
      (node (ref "U1") (pin "D7") (pinfunction "PT2B_D7") (pintype "bidirectional"))
    )
    (net (code "509") (name "unconnected-(U1A-PT3B-PadF7)") (class "Default")
      (node (ref "U1") (pin "F7") (pinfunction "PT3B_F7") (pintype "bidirectional"))
    )
    (net (code "510") (name "unconnected-(U1A-PT4A-PadD4)") (class "Default")
      (node (ref "U1") (pin "D4") (pinfunction "PT4A_D4") (pintype "bidirectional"))
    )
    (net (code "511") (name "unconnected-(U1A-PT4B-PadE7)") (class "Default")
      (node (ref "U1") (pin "E7") (pinfunction "PT4B_E7") (pintype "bidirectional"))
    )
    (net (code "512") (name "unconnected-(U1A-PT6A{slash}TDQS6-PadG7)") (class "Default")
      (node (ref "U1") (pin "G7") (pinfunction "PT6A/TDQS6_G7") (pintype "bidirectional"))
    )
    (net (code "513") (name "unconnected-(U1A-PT7B-PadE8)") (class "Default")
      (node (ref "U1") (pin "E8") (pinfunction "PT7B_E8") (pintype "bidirectional"))
    )
    (net (code "514") (name "unconnected-(U1A-PT8B-PadF8)") (class "Default")
      (node (ref "U1") (pin "F8") (pinfunction "PT8B_F8") (pintype "bidirectional"))
    )
    (net (code "515") (name "unconnected-(U1A-PT11B-PadE9)") (class "Default")
      (node (ref "U1") (pin "E9") (pinfunction "PT11B_E9") (pintype "bidirectional"))
    )
    (net (code "516") (name "unconnected-(U1A-PT12A-PadB6)") (class "Default")
      (node (ref "U1") (pin "B6") (pinfunction "PT12A_B6") (pintype "bidirectional"))
    )
    (net (code "517") (name "unconnected-(U1A-PT14A{slash}TDQS14-PadD9)") (class "Default")
      (node (ref "U1") (pin "D9") (pinfunction "PT14A/TDQS14_D9") (pintype "bidirectional"))
    )
    (net (code "518") (name "unconnected-(U1A-PT15A-PadC9)") (class "Default")
      (node (ref "U1") (pin "C9") (pinfunction "PT15A_C9") (pintype "bidirectional"))
    )
    (net (code "519") (name "unconnected-(U1A-PT18B-PadG10)") (class "Default")
      (node (ref "U1") (pin "G10") (pinfunction "PT18B_G10") (pintype "bidirectional"))
    )
    (net (code "520") (name "unconnected-(U1A-PT19A-PadC7)") (class "Default")
      (node (ref "U1") (pin "C7") (pinfunction "PT19A_C7") (pintype "bidirectional"))
    )
    (net (code "521") (name "unconnected-(U1A-PT20A-PadA7)") (class "Default")
      (node (ref "U1") (pin "A7") (pinfunction "PT20A_A7") (pintype "bidirectional"))
    )
    (net (code "522") (name "unconnected-(U1A-PT20B-PadE11)") (class "Default")
      (node (ref "U1") (pin "E11") (pinfunction "PT20B_E11") (pintype "bidirectional"))
    )
    (net (code "523") (name "unconnected-(U1A-PT21B-PadB8)") (class "Default")
      (node (ref "U1") (pin "B8") (pinfunction "PT21B_B8") (pintype "bidirectional"))
    )
    (net (code "524") (name "unconnected-(U1A-PT23A-PadA8)") (class "Default")
      (node (ref "U1") (pin "A8") (pinfunction "PT23A_A8") (pintype "bidirectional"))
    )
    (net (code "525") (name "unconnected-(U1A-PT29B-PadA12)") (class "Default")
      (node (ref "U1") (pin "A12") (pinfunction "PT29B_A12") (pintype "bidirectional"))
    )
    (net (code "526") (name "unconnected-(U1A-PT31A-PadB13)") (class "Default")
      (node (ref "U1") (pin "B13") (pinfunction "PT31A_B13") (pintype "bidirectional"))
    )
    (net (code "527") (name "unconnected-(U1A-PT31B-PadA13)") (class "Default")
      (node (ref "U1") (pin "A13") (pinfunction "PT31B_A13") (pintype "bidirectional"))
    )
    (net (code "528") (name "unconnected-(U1A-PT32A{slash}VREF2_0-PadC13)") (class "Default")
      (node (ref "U1") (pin "C13") (pinfunction "PT32A/VREF2_0_C13") (pintype "bidirectional"))
    )
    (net (code "529") (name "unconnected-(U1B-PT41B-PadA17)") (class "Default")
      (node (ref "U1") (pin "A17") (pinfunction "PT41B_A17") (pintype "bidirectional"))
    )
    (net (code "530") (name "unconnected-(U1B-PT42A-PadB18)") (class "Default")
      (node (ref "U1") (pin "B18") (pinfunction "PT42A_B18") (pintype "bidirectional"))
    )
    (net (code "531") (name "unconnected-(U1B-PT43A-PadA18)") (class "Default")
      (node (ref "U1") (pin "A18") (pinfunction "PT43A_A18") (pintype "bidirectional"))
    )
    (net (code "532") (name "unconnected-(U1B-PT45A-PadB19)") (class "Default")
      (node (ref "U1") (pin "B19") (pinfunction "PT45A_B19") (pintype "bidirectional"))
    )
    (net (code "533") (name "unconnected-(U1B-PT50A-PadB17)") (class "Default")
      (node (ref "U1") (pin "B17") (pinfunction "PT50A_B17") (pintype "bidirectional"))
    )
    (net (code "534") (name "unconnected-(U1B-PT50B-PadE17)") (class "Default")
      (node (ref "U1") (pin "E17") (pinfunction "PT50B_E17") (pintype "bidirectional"))
    )
    (net (code "535") (name "unconnected-(U1B-PT53A-PadC18)") (class "Default")
      (node (ref "U1") (pin "C18") (pinfunction "PT53A_C18") (pintype "bidirectional"))
    )
    (net (code "536") (name "unconnected-(U1B-PT55A-PadB22)") (class "Default")
      (node (ref "U1") (pin "B22") (pinfunction "PT55A_B22") (pintype "bidirectional"))
    )
    (net (code "537") (name "unconnected-(U1B-PT55B-PadF19)") (class "Default")
      (node (ref "U1") (pin "F19") (pinfunction "PT55B_F19") (pintype "bidirectional"))
    )
    (net (code "538") (name "unconnected-(U1B-PT60A-PadB24)") (class "Default")
      (node (ref "U1") (pin "B24") (pinfunction "PT60A_B24") (pintype "bidirectional"))
    )
    (net (code "539") (name "unconnected-(U1B-PT62B-PadB23)") (class "Default")
      (node (ref "U1") (pin "B23") (pinfunction "PT62B_B23") (pintype "bidirectional"))
    )
    (net (code "540") (name "unconnected-(U1C-PR6B-PadE21)") (class "Default")
      (node (ref "U1") (pin "E21") (pinfunction "PR6B_E21") (pintype "bidirectional"))
    )
    (net (code "541") (name "unconnected-(U1C-PR28B-PadK25)") (class "Default")
      (node (ref "U1") (pin "K25") (pinfunction "PR28B_K25") (pintype "bidirectional"))
    )
    (net (code "542") (name "unconnected-(U1C-PR29B-PadL25)") (class "Default")
      (node (ref "U1") (pin "L25") (pinfunction "PR29B_L25") (pintype "bidirectional"))
    )
    (net (code "543") (name "unconnected-(U1C-PR30B-PadL22)") (class "Default")
      (node (ref "U1") (pin "L22") (pinfunction "PR30B_L22") (pintype "bidirectional"))
    )
    (net (code "544") (name "unconnected-(U1C-PR32A-PadM24)") (class "Default")
      (node (ref "U1") (pin "M24") (pinfunction "PR32A_M24") (pintype "bidirectional"))
    )
    (net (code "545") (name "unconnected-(U1C-PR32B-PadM25)") (class "Default")
      (node (ref "U1") (pin "M25") (pinfunction "PR32B_M25") (pintype "bidirectional"))
    )
    (net (code "546") (name "unconnected-(U1C-PR33A-PadM23)") (class "Default")
      (node (ref "U1") (pin "M23") (pinfunction "PR33A_M23") (pintype "bidirectional"))
    )
    (net (code "547") (name "unconnected-(U1C-PR34B{slash}PCLKC2_0-PadL26)") (class "Default")
      (node (ref "U1") (pin "L26") (pinfunction "PR34B/PCLKC2_0_L26") (pintype "bidirectional"))
    )
    (net (code "548") (name "unconnected-(U1D-PR36A-PadN24)") (class "Default")
      (node (ref "U1") (pin "N24") (pinfunction "PR36A_N24") (pintype "bidirectional"))
    )
    (net (code "549") (name "unconnected-(U1D-PR36B-PadN25)") (class "Default")
      (node (ref "U1") (pin "N25") (pinfunction "PR36B_N25") (pintype "bidirectional"))
    )
    (net (code "550") (name "unconnected-(U1D-PR38B-PadN21)") (class "Default")
      (node (ref "U1") (pin "N21") (pinfunction "PR38B_N21") (pintype "bidirectional"))
    )
    (net (code "551") (name "unconnected-(U1D-PR39A-PadM26)") (class "Default")
      (node (ref "U1") (pin "M26") (pinfunction "PR39A_M26") (pintype "bidirectional"))
    )
    (net (code "552") (name "unconnected-(U1D-PR39B-PadN26)") (class "Default")
      (node (ref "U1") (pin "N26") (pinfunction "PR39B_N26") (pintype "bidirectional"))
    )
    (net (code "553") (name "unconnected-(U1D-PR41B-PadP25)") (class "Default")
      (node (ref "U1") (pin "P25") (pinfunction "PR41B_P25") (pintype "bidirectional"))
    )
    (net (code "554") (name "unconnected-(U1E-PB34A{slash}WRITEN-PadAA13)") (class "Default")
      (node (ref "U1") (pin "AA13") (pinfunction "PB34A/WRITEN_AA13") (pintype "bidirectional"))
    )
    (net (code "555") (name "unconnected-(U1E-PB35A{slash}VREF1_4-PadAD14)") (class "Default")
      (node (ref "U1") (pin "AD14") (pinfunction "PB35A/VREF1_4_AD14") (pintype "bidirectional"))
    )
    (net (code "556") (name "unconnected-(U1E-PB36B{slash}D0{slash}SPID7-PadAB14)") (class "Default")
      (node (ref "U1") (pin "AB14") (pinfunction "PB36B/D0/SPID7_AB14") (pintype "bidirectional"))
    )
    (net (code "557") (name "unconnected-(U1E-PB38B{slash}D3{slash}SPID4-PadAC15)") (class "Default")
      (node (ref "U1") (pin "AC15") (pinfunction "PB38B/D3/SPID4_AC15") (pintype "bidirectional"))
    )
    (net (code "558") (name "unconnected-(U1E-PB61B-PadAE25)") (class "Default")
      (node (ref "U1") (pin "AE25") (pinfunction "PB61B_AE25") (pintype "bidirectional"))
    )
    (net (code "559") (name "unconnected-(U1F-PB5B-PadAC5)") (class "Default")
      (node (ref "U1") (pin "AC5") (pinfunction "PB5B_AC5") (pintype "bidirectional"))
    )
    (net (code "560") (name "unconnected-(U1F-PB9A-PadAD5)") (class "Default")
      (node (ref "U1") (pin "AD5") (pinfunction "PB9A_AD5") (pintype "bidirectional"))
    )
    (net (code "561") (name "unconnected-(U1F-PB9B-PadAD4)") (class "Default")
      (node (ref "U1") (pin "AD4") (pinfunction "PB9B_AD4") (pintype "bidirectional"))
    )
    (net (code "562") (name "unconnected-(U1F-PB10B-PadAC9)") (class "Default")
      (node (ref "U1") (pin "AC9") (pinfunction "PB10B_AC9") (pintype "bidirectional"))
    )
    (net (code "563") (name "unconnected-(U1F-PB31A-PadAE13)") (class "Default")
      (node (ref "U1") (pin "AE13") (pinfunction "PB31A_AE13") (pintype "bidirectional"))
    )
    (net (code "564") (name "unconnected-(U1G-PL36B-PadP2)") (class "Default")
      (node (ref "U1") (pin "P2") (pinfunction "PL36B_P2") (pintype "bidirectional"))
    )
    (net (code "565") (name "unconnected-(U1G-PL37A-PadL7)") (class "Default")
      (node (ref "U1") (pin "L7") (pinfunction "PL37A_L7") (pintype "bidirectional"))
    )
    (net (code "566") (name "unconnected-(U1G-PL37B-PadL6)") (class "Default")
      (node (ref "U1") (pin "L6") (pinfunction "PL37B_L6") (pintype "bidirectional"))
    )
    (net (code "567") (name "unconnected-(U1G-PL38A-PadN4)") (class "Default")
      (node (ref "U1") (pin "N4") (pinfunction "PL38A_N4") (pintype "bidirectional"))
    )
    (net (code "568") (name "unconnected-(U1G-PL38B-PadN5)") (class "Default")
      (node (ref "U1") (pin "N5") (pinfunction "PL38B_N5") (pintype "bidirectional"))
    )
    (net (code "569") (name "unconnected-(U1G-PL41B-PadM6)") (class "Default")
      (node (ref "U1") (pin "M6") (pinfunction "PL41B_M6") (pintype "bidirectional"))
    )
    (net (code "570") (name "unconnected-(U1G-PL44A-PadN6)") (class "Default")
      (node (ref "U1") (pin "N6") (pinfunction "PL44A_N6") (pintype "bidirectional"))
    )
    (net (code "571") (name "unconnected-(U1G-PL44B-PadP5)") (class "Default")
      (node (ref "U1") (pin "P5") (pinfunction "PL44B_P5") (pintype "bidirectional"))
    )
    (net (code "572") (name "unconnected-(U1G-PL54A{slash}LLM0_PLLT_FB_A-PadV6)") (class "Default")
      (node (ref "U1") (pin "V6") (pinfunction "PL54A/LLM0_PLLT_FB_A_V6") (pintype "bidirectional"))
    )
    (net (code "573") (name "unconnected-(U1G-PL63B-PadAB3)") (class "Default")
      (node (ref "U1") (pin "AB3") (pinfunction "PL63B_AB3") (pintype "bidirectional"))
    )
    (net (code "574") (name "unconnected-(U1H-PL2B{slash}VREF1_7-PadE4)") (class "Default")
      (node (ref "U1") (pin "E4") (pinfunction "PL2B/VREF1_7_E4") (pintype "bidirectional"))
    )
    (net (code "575") (name "unconnected-(U1H-PL7B-PadF5)") (class "Default")
      (node (ref "U1") (pin "F5") (pinfunction "PL7B_F5") (pintype "bidirectional"))
    )
    (net (code "576") (name "unconnected-(U1H-PL19A-PadH6)") (class "Default")
      (node (ref "U1") (pin "H6") (pinfunction "PL19A_H6") (pintype "bidirectional"))
    )
    (net (code "577") (name "unconnected-(U1H-PL19B-PadJ7)") (class "Default")
      (node (ref "U1") (pin "J7") (pinfunction "PL19B_J7") (pintype "bidirectional"))
    )
    (net (code "578") (name "unconnected-(U1H-PL20A-PadG5)") (class "Default")
      (node (ref "U1") (pin "G5") (pinfunction "PL20A_G5") (pintype "bidirectional"))
    )
    (net (code "579") (name "unconnected-(U1H-PL20B-PadH5)") (class "Default")
      (node (ref "U1") (pin "H5") (pinfunction "PL20B_H5") (pintype "bidirectional"))
    )
    (net (code "580") (name "unconnected-(U1H-PL23B-PadJ5)") (class "Default")
      (node (ref "U1") (pin "J5") (pinfunction "PL23B_J5") (pintype "bidirectional"))
    )
    (net (code "581") (name "unconnected-(U1H-PL24B-PadK5)") (class "Default")
      (node (ref "U1") (pin "K5") (pinfunction "PL24B_K5") (pintype "bidirectional"))
    )
    (net (code "582") (name "unconnected-(U1H-PL25A-PadJ6)") (class "Default")
      (node (ref "U1") (pin "J6") (pinfunction "PL25A_J6") (pintype "bidirectional"))
    )
    (net (code "583") (name "unconnected-(U1H-PL25B-PadK6)") (class "Default")
      (node (ref "U1") (pin "K6") (pinfunction "PL25B_K6") (pintype "bidirectional"))
    )
    (net (code "584") (name "unconnected-(U1H-PL32A-PadM1)") (class "Default")
      (node (ref "U1") (pin "M1") (pinfunction "PL32A_M1") (pintype "bidirectional"))
    )
    (net (code "585") (name "unconnected-(U1H-PL33B-PadL5)") (class "Default")
      (node (ref "U1") (pin "L5") (pinfunction "PL33B_L5") (pintype "bidirectional"))
    )
  )
)
